# 31813C.net
KiCad netlist of a schematic drawn in EAGLE
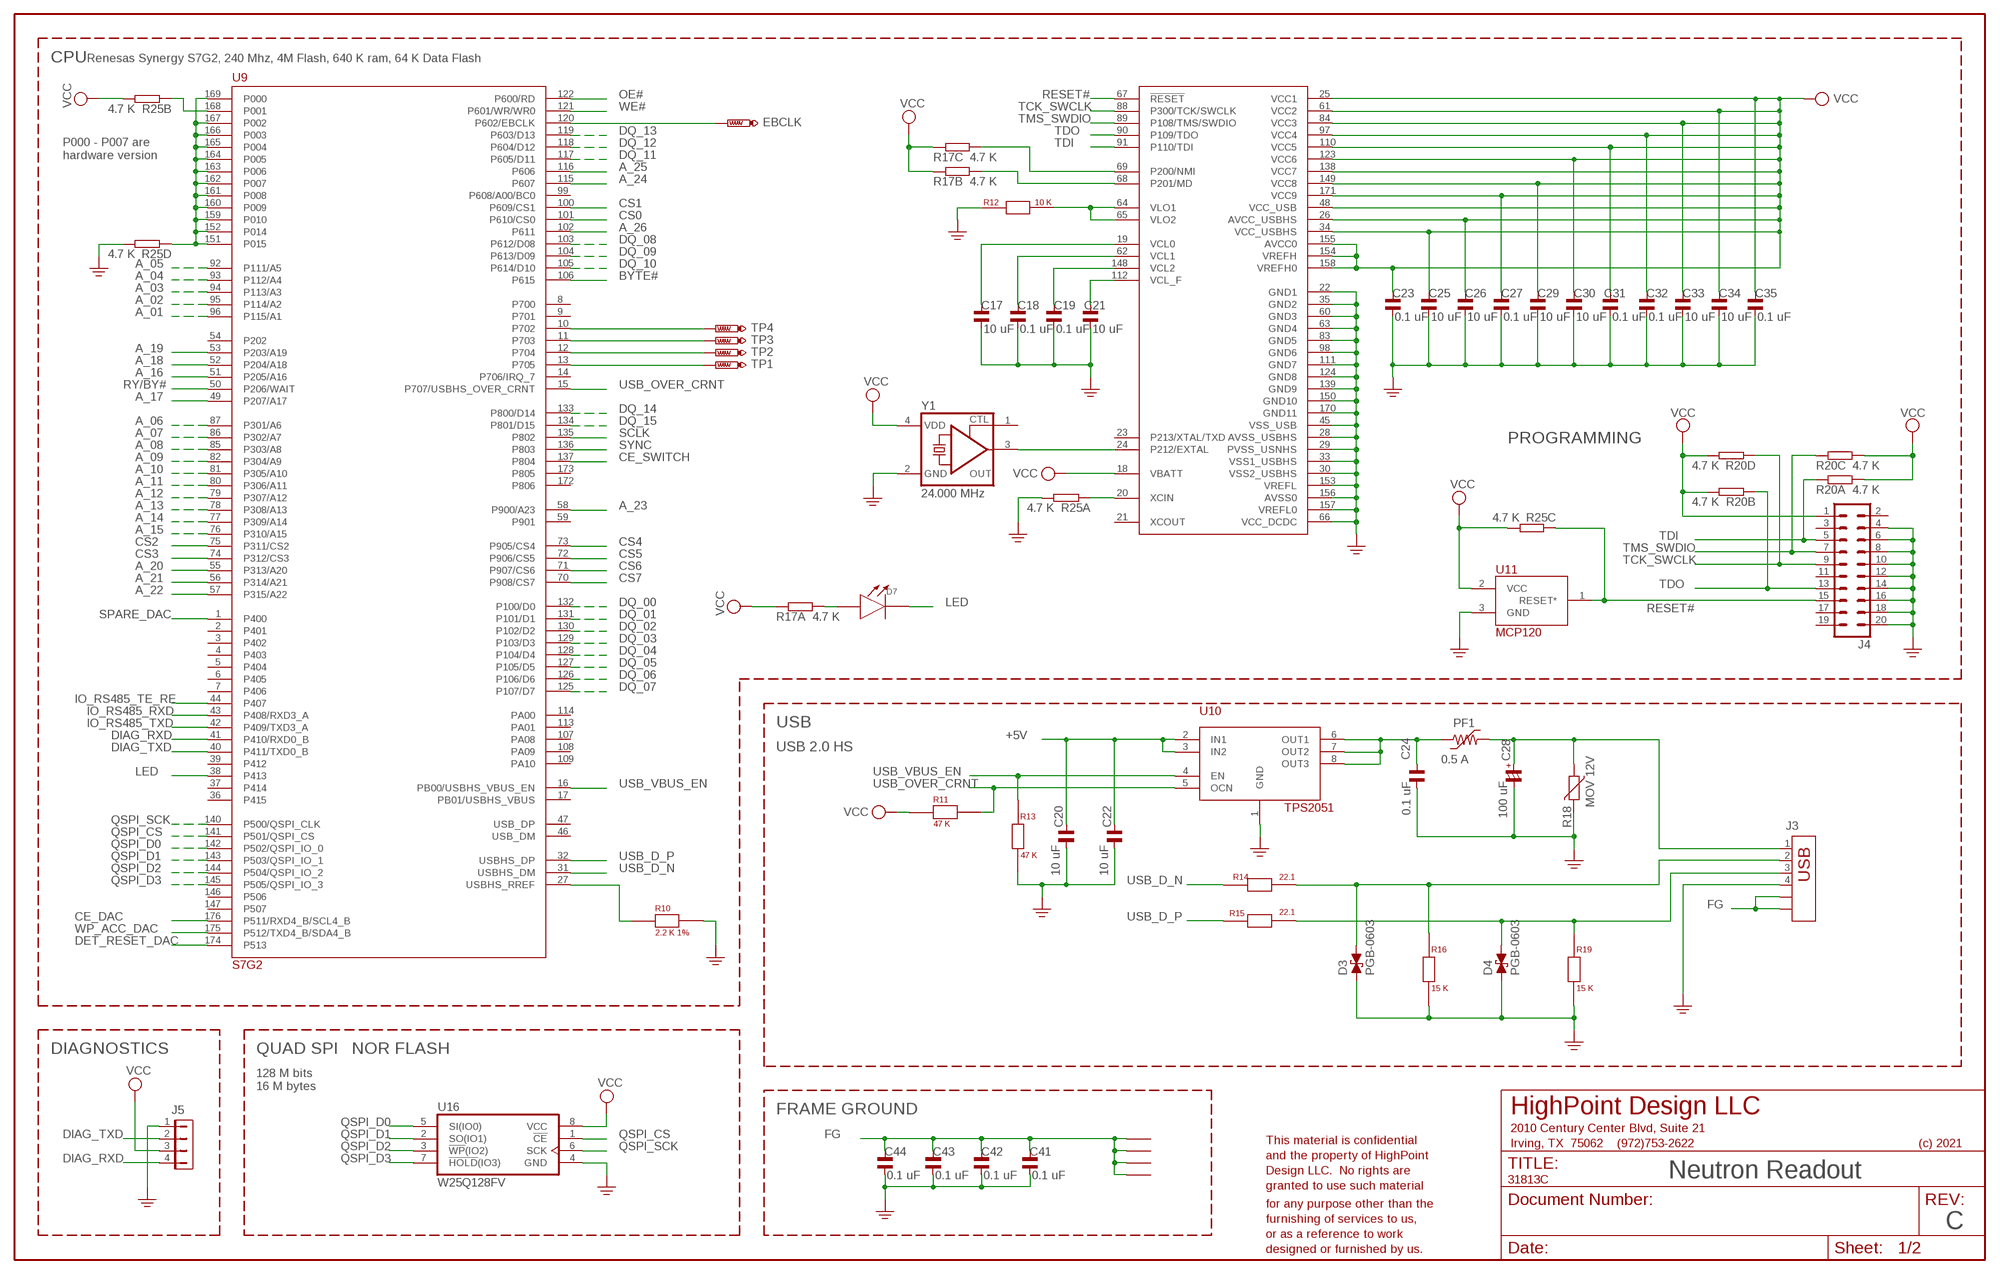
[diagram p0: schematic, sheet 1]
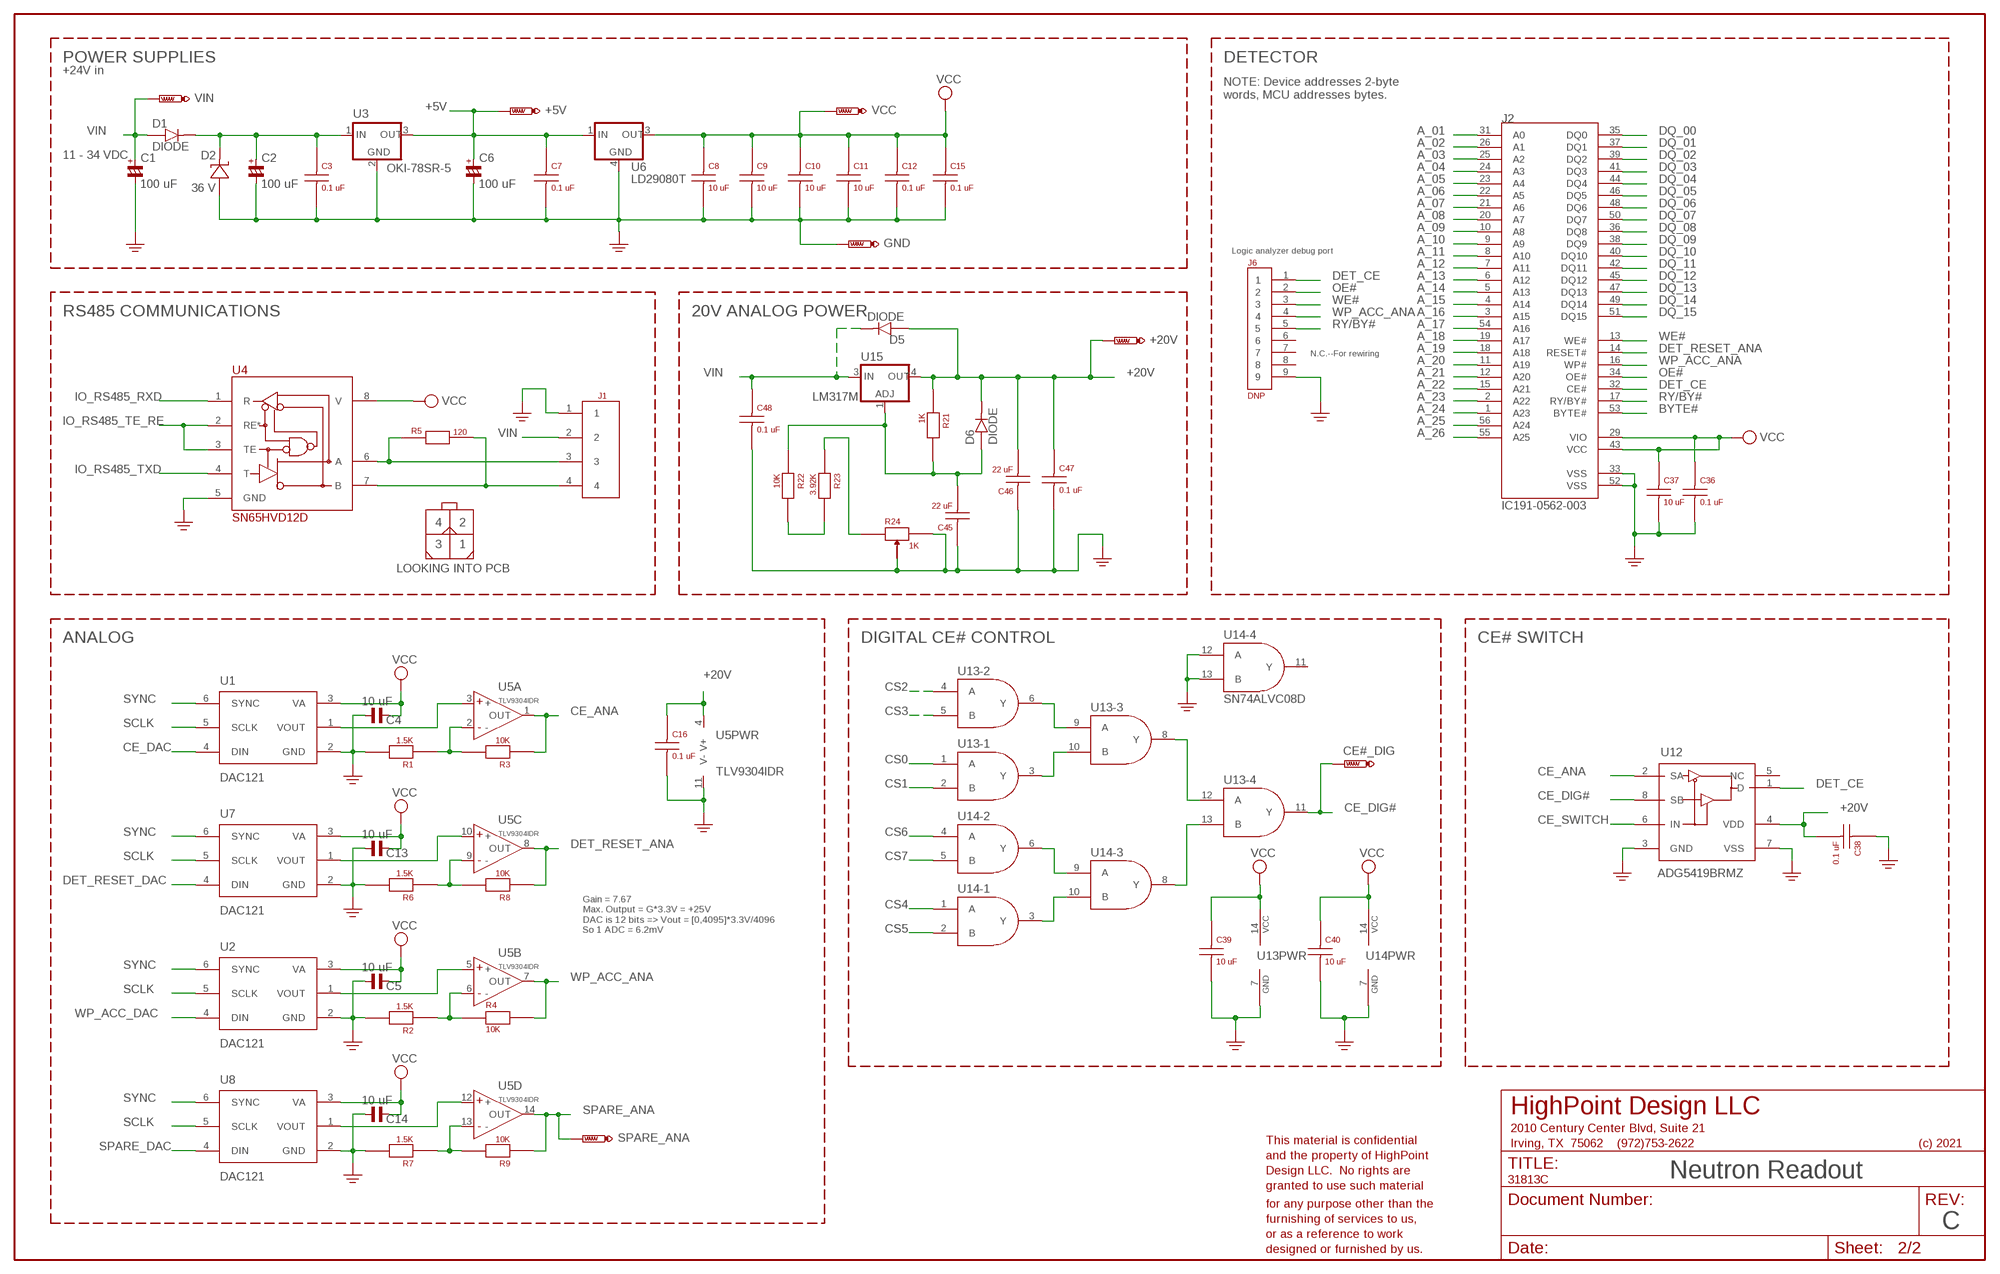
[diagram p1: schematic, sheet 2]

(export (version "E")
  (design (tool "Eeschema 10.0.6"))
  (components
    (comp (ref "+5V")
      (value "TP")
      (footprint "eagle-import:TP8040")
      (libsource (lib "eagle-import") (part "TP"))
    )
    (comp (ref "+20V")
      (value "TP")
      (footprint "eagle-import:TP8040")
      (libsource (lib "eagle-import") (part "TP"))
    )
    (comp (ref "C1")
      (value "100 uF")
      (footprint "eagle-import:CSV-E_F")
      (libsource (lib "eagle-import") (part "CAP_POL-E"))
    )
    (comp (ref "C2")
      (value "100 uF")
      (footprint "eagle-import:CSV-E_F")
      (libsource (lib "eagle-import") (part "CAP_POL-E"))
    )
    (comp (ref "C3")
      (value "0.1 uF")
      (footprint "eagle-import:0603")
      (libsource (lib "eagle-import") (part "CAP-0603"))
    )
    (comp (ref "C4")
      (value "10 uF")
      (footprint "eagle-import:0603")
      (libsource (lib "eagle-import") (part "CAP_SMD-0603"))
    )
    (comp (ref "C5")
      (value "10 uF")
      (footprint "eagle-import:0603")
      (libsource (lib "eagle-import") (part "CAP_SMD-0603"))
    )
    (comp (ref "C6")
      (value "100 uF")
      (footprint "eagle-import:CSV-E_F")
      (libsource (lib "eagle-import") (part "CAP_POL-E"))
    )
    (comp (ref "C7")
      (value "0.1 uF")
      (footprint "eagle-import:0603")
      (libsource (lib "eagle-import") (part "CAP-0603"))
    )
    (comp (ref "C8")
      (value "10 uF")
      (footprint "eagle-import:0603")
      (libsource (lib "eagle-import") (part "CAP-0603"))
    )
    (comp (ref "C9")
      (value "10 uF")
      (footprint "eagle-import:0603")
      (libsource (lib "eagle-import") (part "CAP-0603"))
    )
    (comp (ref "C10")
      (value "10 uF")
      (footprint "eagle-import:0603")
      (libsource (lib "eagle-import") (part "CAP-0603"))
    )
    (comp (ref "C11")
      (value "10 uF")
      (footprint "eagle-import:0603")
      (libsource (lib "eagle-import") (part "CAP-0603"))
    )
    (comp (ref "C12")
      (value "0.1 uF")
      (footprint "eagle-import:0603")
      (libsource (lib "eagle-import") (part "CAP-0603"))
    )
    (comp (ref "C13")
      (value "10 uF")
      (footprint "eagle-import:0603")
      (libsource (lib "eagle-import") (part "CAP_SMD-0603"))
    )
    (comp (ref "C14")
      (value "10 uF")
      (footprint "eagle-import:0603")
      (libsource (lib "eagle-import") (part "CAP_SMD-0603"))
    )
    (comp (ref "C15")
      (value "0.1 uF")
      (footprint "eagle-import:0603")
      (libsource (lib "eagle-import") (part "CAP-0603"))
    )
    (comp (ref "C16")
      (value "0.1 uF")
      (footprint "eagle-import:0603")
      (libsource (lib "eagle-import") (part "CAP-0603"))
    )
    (comp (ref "C36")
      (value "0.1 uF")
      (footprint "eagle-import:0603")
      (libsource (lib "eagle-import") (part "CAP-0603"))
    )
    (comp (ref "C37")
      (value "10 uF")
      (footprint "eagle-import:0603")
      (libsource (lib "eagle-import") (part "CAP-0603"))
    )
    (comp (ref "C38")
      (value "0.1 uF")
      (footprint "eagle-import:0603")
      (libsource (lib "eagle-import") (part "CAP-0603"))
    )
    (comp (ref "C39")
      (value "10 uF")
      (footprint "eagle-import:0603")
      (libsource (lib "eagle-import") (part "CAP-0603"))
    )
    (comp (ref "C40")
      (value "10 uF")
      (footprint "eagle-import:0603")
      (libsource (lib "eagle-import") (part "CAP-0603"))
    )
    (comp (ref "C45")
      (value "22 uF")
      (footprint "eagle-import:C1206")
      (libsource (lib "eagle-import") (part "CAP-1206"))
    )
    (comp (ref "C46")
      (value "22 uF")
      (footprint "eagle-import:C1206")
      (libsource (lib "eagle-import") (part "CAP-1206"))
    )
    (comp (ref "C47")
      (value "0.1 uF")
      (footprint "eagle-import:0603")
      (libsource (lib "eagle-import") (part "CAP-0603"))
    )
    (comp (ref "C48")
      (value "0.1 uF")
      (footprint "eagle-import:0603")
      (libsource (lib "eagle-import") (part "CAP-0603"))
    )
    (comp (ref "CE#_DIG")
      (value "TP")
      (footprint "eagle-import:TP8040")
      (libsource (lib "eagle-import") (part "TP"))
    )
    (comp (ref "D1")
      (value "DIODE")
      (footprint "eagle-import:SOD-123_MINI-SMA")
      (libsource (lib "eagle-import") (part "DIODE"))
    )
    (comp (ref "D2")
      (value "36 V")
      (footprint "eagle-import:SMB")
      (libsource (lib "eagle-import") (part "TRANSORB"))
    )
    (comp (ref "D5")
      (value "DIODE")
      (footprint "eagle-import:SOD-123_MINI-SMA")
      (libsource (lib "eagle-import") (part "DIODE"))
    )
    (comp (ref "D6")
      (value "DIODE")
      (footprint "eagle-import:SOD-123_MINI-SMA")
      (libsource (lib "eagle-import") (part "DIODE"))
    )
    (comp (ref "GND")
      (value "TP")
      (footprint "eagle-import:TP8040")
      (libsource (lib "eagle-import") (part "TP"))
    )
    (comp (ref "J1")
      (value "MICRO-FIT-4POS")
      (footprint "eagle-import:43045-0412")
      (libsource (lib "eagle-import") (part "MICRO-FIT-4POS"))
    )
    (comp (ref "J2")
      (value "IC191-0562-003")
      (footprint "eagle-import:IC1910562003")
      (fields (field (name "MOUSER_PART_NUMBER") "945-IC191-0562-003"))
      (libsource (lib "eagle-import") (part "IC191-0562-003"))
    )
    (comp (ref "J6")
      (value "DNP")
      (footprint "eagle-import:9P-100")
      (libsource (lib "eagle-import") (part "CON-9P-100"))
    )
    (comp (ref "R1")
      (value "1.5K")
      (footprint "eagle-import:0603")
      (libsource (lib "eagle-import") (part "RES-0603-H"))
    )
    (comp (ref "R2")
      (value "1.5K")
      (footprint "eagle-import:0603")
      (libsource (lib "eagle-import") (part "RES-0603-H"))
    )
    (comp (ref "R3")
      (value "10K")
      (footprint "eagle-import:0603")
      (libsource (lib "eagle-import") (part "RES-0603-H"))
    )
    (comp (ref "R4")
      (value "10K")
      (footprint "eagle-import:0603")
      (libsource (lib "eagle-import") (part "RES-0603-H"))
    )
    (comp (ref "R5")
      (value "120")
      (footprint "eagle-import:0603")
      (libsource (lib "eagle-import") (part "RES-0603-H"))
    )
    (comp (ref "R6")
      (value "1.5K")
      (footprint "eagle-import:0603")
      (libsource (lib "eagle-import") (part "RES-0603-H"))
    )
    (comp (ref "R7")
      (value "1.5K")
      (footprint "eagle-import:0603")
      (libsource (lib "eagle-import") (part "RES-0603-H"))
    )
    (comp (ref "R8")
      (value "10K")
      (footprint "eagle-import:0603")
      (libsource (lib "eagle-import") (part "RES-0603-H"))
    )
    (comp (ref "R9")
      (value "10K")
      (footprint "eagle-import:0603")
      (libsource (lib "eagle-import") (part "RES-0603-H"))
    )
    (comp (ref "R21")
      (value "1K")
      (footprint "eagle-import:0603")
      (libsource (lib "eagle-import") (part "RES-0603-H"))
    )
    (comp (ref "R22")
      (value "10K")
      (footprint "eagle-import:0603")
      (libsource (lib "eagle-import") (part "RES-0603-H"))
    )
    (comp (ref "R23")
      (value "3.92K")
      (footprint "eagle-import:0603")
      (libsource (lib "eagle-import") (part "RES-0603-H"))
    )
    (comp (ref "R24")
      (value "1K")
      (footprint "eagle-import:POT-V10")
      (libsource (lib "eagle-import") (part "PT10XV10"))
    )
    (comp (ref "SPARE_ANA")
      (value "TP")
      (footprint "eagle-import:TP8040")
      (libsource (lib "eagle-import") (part "TP"))
    )
    (comp (ref "U1")
      (value "DAC121")
      (footprint "eagle-import:SOT23-6")
      (libsource (lib "eagle-import") (part "DAC121"))
    )
    (comp (ref "U2")
      (value "DAC121")
      (footprint "eagle-import:SOT23-6")
      (libsource (lib "eagle-import") (part "DAC121"))
    )
    (comp (ref "U3")
      (value "OKI-78SR-5")
      (footprint "eagle-import:PS-OKI-78SR")
      (libsource (lib "eagle-import") (part "PS-OKI-78SR"))
    )
    (comp (ref "U4")
      (value "SN65HVD12D")
      (footprint "eagle-import:SOIC-08-150")
      (libsource (lib "eagle-import") (part "SN65HVD12D"))
    )
    (comp (ref "U5")
      (value "TLV9304IDR")
      (footprint "eagle-import:SO14")
      (libsource (lib "eagle-import") (part "TLV9304IDR"))
    )
    (comp (ref "U6")
      (value "LD29080T")
      (footprint "eagle-import:DPAK")
      (libsource (lib "eagle-import") (part "LD29080T"))
    )
    (comp (ref "U7")
      (value "DAC121")
      (footprint "eagle-import:SOT23-6")
      (libsource (lib "eagle-import") (part "DAC121"))
    )
    (comp (ref "U8")
      (value "DAC121")
      (footprint "eagle-import:SOT23-6")
      (libsource (lib "eagle-import") (part "DAC121"))
    )
    (comp (ref "U12")
      (value "ADG5419BRMZ")
      (footprint "eagle-import:RM_8_ADI")
      (libsource (lib "eagle-import") (part "ADG5419BRMZ"))
    )
    (comp (ref "U13")
      (value "SN74ALVC08D")
      (footprint "eagle-import:D14")
      (fields
        (field (name "GENERIC_PART_NUMBER") "SN74ALVC08")
        (field (name "MANUFACTURER") "Texas Instruments")
      )
      (libsource (lib "eagle-import") (part "SN74ALVC08D"))
    )
    (comp (ref "U14")
      (value "SN74ALVC08D")
      (footprint "eagle-import:D14")
      (fields
        (field (name "GENERIC_PART_NUMBER") "SN74ALVC08")
        (field (name "MANUFACTURER") "Texas Instruments")
      )
      (libsource (lib "eagle-import") (part "SN74ALVC08D"))
    )
    (comp (ref "U15")
      (value "LM317M")
      (footprint "eagle-import:DPAK")
      (libsource (lib "eagle-import") (part "LM317M"))
    )
    (comp (ref "VCC")
      (value "TP")
      (footprint "eagle-import:TP8040")
      (libsource (lib "eagle-import") (part "TP"))
    )
    (comp (ref "VIN")
      (value "TP")
      (footprint "eagle-import:TP8040")
      (libsource (lib "eagle-import") (part "TP"))
    )
    (comp (ref "C17")
      (value "10 uF")
      (footprint "eagle-import:0603")
      (libsource (lib "eagle-import") (part "CAP_SMD-0603"))
    )
    (comp (ref "C18")
      (value "0.1 uF")
      (footprint "eagle-import:0603")
      (libsource (lib "eagle-import") (part "CAP_SMD-0603"))
    )
    (comp (ref "C19")
      (value "0.1 uF")
      (footprint "eagle-import:0603")
      (libsource (lib "eagle-import") (part "CAP_SMD-0603"))
    )
    (comp (ref "C20")
      (value "10 uF")
      (footprint "eagle-import:0603")
      (libsource (lib "eagle-import") (part "CAP_SMD-0603"))
    )
    (comp (ref "C21")
      (value "10 uF")
      (footprint "eagle-import:0603")
      (libsource (lib "eagle-import") (part "CAP_SMD-0603"))
    )
    (comp (ref "C22")
      (value "10 uF")
      (footprint "eagle-import:0603")
      (libsource (lib "eagle-import") (part "CAP_SMD-0603"))
    )
    (comp (ref "C23")
      (value "0.1 uF")
      (footprint "eagle-import:0603")
      (libsource (lib "eagle-import") (part "CAP_SMD-0603"))
    )
    (comp (ref "C24")
      (value "0.1 uF")
      (footprint "eagle-import:0603")
      (libsource (lib "eagle-import") (part "CAP_SMD-0603"))
    )
    (comp (ref "C25")
      (value "10 uF")
      (footprint "eagle-import:0603")
      (libsource (lib "eagle-import") (part "CAP_SMD-0603"))
    )
    (comp (ref "C26")
      (value "10 uF")
      (footprint "eagle-import:0603")
      (libsource (lib "eagle-import") (part "CAP_SMD-0603"))
    )
    (comp (ref "C27")
      (value "0.1 uF")
      (footprint "eagle-import:0603")
      (libsource (lib "eagle-import") (part "CAP_SMD-0603"))
    )
    (comp (ref "C28")
      (value "100 uF")
      (footprint "eagle-import:CSV-E_F")
      (libsource (lib "eagle-import") (part "CAP_POL-E"))
    )
    (comp (ref "C29")
      (value "10 uF")
      (footprint "eagle-import:0603")
      (libsource (lib "eagle-import") (part "CAP_SMD-0603"))
    )
    (comp (ref "C30")
      (value "10 uF")
      (footprint "eagle-import:0603")
      (libsource (lib "eagle-import") (part "CAP_SMD-0603"))
    )
    (comp (ref "C31")
      (value "0.1 uF")
      (footprint "eagle-import:0603")
      (libsource (lib "eagle-import") (part "CAP_SMD-0603"))
    )
    (comp (ref "C32")
      (value "0.1 uF")
      (footprint "eagle-import:0603")
      (libsource (lib "eagle-import") (part "CAP_SMD-0603"))
    )
    (comp (ref "C33")
      (value "10 uF")
      (footprint "eagle-import:0603")
      (libsource (lib "eagle-import") (part "CAP_SMD-0603"))
    )
    (comp (ref "C34")
      (value "10 uF")
      (footprint "eagle-import:0603")
      (libsource (lib "eagle-import") (part "CAP_SMD-0603"))
    )
    (comp (ref "C35")
      (value "0.1 uF")
      (footprint "eagle-import:0603")
      (libsource (lib "eagle-import") (part "CAP_SMD-0603"))
    )
    (comp (ref "C41")
      (value "0.1 uF")
      (footprint "eagle-import:0603")
      (libsource (lib "eagle-import") (part "CAP_SMD-0603"))
    )
    (comp (ref "C42")
      (value "0.1 uF")
      (footprint "eagle-import:0603")
      (libsource (lib "eagle-import") (part "CAP_SMD-0603"))
    )
    (comp (ref "C43")
      (value "0.1 uF")
      (footprint "eagle-import:0603")
      (libsource (lib "eagle-import") (part "CAP_SMD-0603"))
    )
    (comp (ref "C44")
      (value "0.1 uF")
      (footprint "eagle-import:0603")
      (libsource (lib "eagle-import") (part "CAP_SMD-0603"))
    )
    (comp (ref "D3")
      (value "PGB-0603")
      (footprint "eagle-import:PGB-0603")
      (libsource (lib "eagle-import") (part "PGB-0603"))
    )
    (comp (ref "D4")
      (value "PGB-0603")
      (footprint "eagle-import:PGB-0603")
      (libsource (lib "eagle-import") (part "PGB-0603"))
    )
    (comp (ref "D7")
      (value "LED0805")
      (footprint "eagle-import:D0805")
      (libsource (lib "eagle-import") (part "LED0805"))
    )
    (comp (ref "EBCLK")
      (value "TP")
      (footprint "eagle-import:TP8040")
      (libsource (lib "eagle-import") (part "TP"))
    )
    (comp (ref "J3")
      (value "CON-USB-292303-1")
      (footprint "eagle-import:USB")
      (libsource (lib "eagle-import") (part "CON-USB-292303-1"))
    )
    (comp (ref "J4")
      (value "ML20")
      (footprint "eagle-import:ML20")
      (libsource (lib "eagle-import") (part "ML20"))
    )
    (comp (ref "J5")
      (value "MTA04")
      (footprint "eagle-import:MTA04-100")
      (libsource (lib "eagle-import") (part "MTA04"))
    )
    (comp (ref "M1")
      (value "MNT-125")
      (footprint "eagle-import:MNT-125")
      (libsource (lib "eagle-import") (part "MNT-125"))
    )
    (comp (ref "M2")
      (value "MNT-125")
      (footprint "eagle-import:MNT-125")
      (libsource (lib "eagle-import") (part "MNT-125"))
    )
    (comp (ref "M3")
      (value "MNT-125")
      (footprint "eagle-import:MNT-125")
      (libsource (lib "eagle-import") (part "MNT-125"))
    )
    (comp (ref "M4")
      (value "MNT-125")
      (footprint "eagle-import:MNT-125")
      (libsource (lib "eagle-import") (part "MNT-125"))
    )
    (comp (ref "PF1")
      (value "0.5 A")
      (footprint "eagle-import:F1206")
      (libsource (lib "eagle-import") (part "PTC-F1206"))
    )
    (comp (ref "R10")
      (value "2.2 K 1%")
      (footprint "eagle-import:0603")
      (libsource (lib "eagle-import") (part "RES-0603-H"))
    )
    (comp (ref "R11")
      (value "47 K")
      (footprint "eagle-import:0603")
      (libsource (lib "eagle-import") (part "RES-0603-H"))
    )
    (comp (ref "R12")
      (value "10 K")
      (footprint "eagle-import:0603")
      (libsource (lib "eagle-import") (part "RES-0603-H"))
    )
    (comp (ref "R13")
      (value "47 K")
      (footprint "eagle-import:0603")
      (libsource (lib "eagle-import") (part "RES-0603-V"))
    )
    (comp (ref "R14")
      (value "22.1")
      (footprint "eagle-import:0603")
      (libsource (lib "eagle-import") (part "RES-0603-H"))
    )
    (comp (ref "R15")
      (value "22.1")
      (footprint "eagle-import:0603")
      (libsource (lib "eagle-import") (part "RES-0603-H"))
    )
    (comp (ref "R16")
      (value "15 K")
      (footprint "eagle-import:0603")
      (libsource (lib "eagle-import") (part "RES-0603-V"))
    )
    (comp (ref "R17")
      (value "4.7 K")
      (footprint "eagle-import:RNET-4R-38V")
      (libsource (lib "eagle-import") (part "R_38V"))
    )
    (comp (ref "R18")
      (value "MOV 12V")
      (footprint "eagle-import:R0603")
      (libsource (lib "eagle-import") (part "VARISTOR-0603"))
    )
    (comp (ref "R19")
      (value "15 K")
      (footprint "eagle-import:0603")
      (libsource (lib "eagle-import") (part "RES-0603-V"))
    )
    (comp (ref "R20")
      (value "4.7 K")
      (footprint "eagle-import:RNET-4R-38V")
      (libsource (lib "eagle-import") (part "R_38V"))
    )
    (comp (ref "R25")
      (value "4.7 K")
      (footprint "eagle-import:RNET-4R-38V")
      (libsource (lib "eagle-import") (part "R_38V"))
    )
    (comp (ref "TP1")
      (value "TP")
      (footprint "eagle-import:TP8040")
      (libsource (lib "eagle-import") (part "TP"))
    )
    (comp (ref "TP2")
      (value "TP")
      (footprint "eagle-import:TP8040")
      (libsource (lib "eagle-import") (part "TP"))
    )
    (comp (ref "TP3")
      (value "TP")
      (footprint "eagle-import:TP8040")
      (libsource (lib "eagle-import") (part "TP"))
    )
    (comp (ref "TP4")
      (value "TP")
      (footprint "eagle-import:TP8040")
      (libsource (lib "eagle-import") (part "TP"))
    )
    (comp (ref "U9")
      (value "S7G2")
      (footprint "eagle-import:LQFP176")
      (libsource (lib "eagle-import") (part "S7G2-176"))
    )
    (comp (ref "U10")
      (value "TPS2051")
      (footprint "eagle-import:SOIC-8-SPECIAL")
      (libsource (lib "eagle-import") (part "TPS2051"))
    )
    (comp (ref "U11")
      (value "MCP120")
      (footprint "eagle-import:SOT23")
      (libsource (lib "eagle-import") (part "MCP120"))
    )
    (comp (ref "U16")
      (value "W25Q128FV")
      (footprint "eagle-import:SO08-JB")
      (libsource (lib "eagle-import") (part "IS25LQ080B-JB"))
    )
    (comp (ref "Y1")
      (value "24.000 MHz")
      (footprint "eagle-import:ASFL1")
      (libsource (lib "eagle-import") (part "ASFL1"))
    )
  )
  (nets
    (net (code "1") (name "+5V") (class "Default")
      (node (ref "+5V") (pin "1") (pinfunction "TP_1") (pintype "input"))
      (node (ref "C20") (pin "2") (pinfunction "2_2") (pintype "passive"))
      (node (ref "C22") (pin "2") (pinfunction "2_2") (pintype "passive"))
      (node (ref "C6") (pin "+") (pinfunction "+_+") (pintype "passive"))
      (node (ref "C7") (pin "1") (pinfunction "P$1_1") (pintype "bidirectional"))
      (node (ref "U10") (pin "2") (pinfunction "IN1_2") (pintype "bidirectional"))
      (node (ref "U10") (pin "3") (pinfunction "IN2_3") (pintype "bidirectional"))
      (node (ref "U3") (pin "3") (pinfunction "OUT_3") (pintype "passive"))
      (node (ref "U6") (pin "1") (pinfunction "IN_1") (pintype "input"))
    )
    (net (code "2") (name "+20V") (class "Default")
      (node (ref "+20V") (pin "1") (pinfunction "TP_1") (pintype "input"))
      (node (ref "C16") (pin "1") (pinfunction "P$1_1") (pintype "bidirectional"))
      (node (ref "C38") (pin "2") (pinfunction "P$2_2") (pintype "bidirectional"))
      (node (ref "C46") (pin "2") (pinfunction "P$2_2") (pintype "bidirectional"))
      (node (ref "C47") (pin "1") (pinfunction "P$1_1") (pintype "bidirectional"))
      (node (ref "D5") (pin "A") (pinfunction "A_A") (pintype "passive"))
      (node (ref "D6") (pin "C") (pinfunction "C_C") (pintype "passive"))
      (node (ref "R21") (pin "1") (pinfunction "P$1_1") (pintype "bidirectional"))
      (node (ref "U12") (pin "4") (pinfunction "VDD_4") (pintype "passive"))
      (node (ref "U15") (pin "4") (pinfunction "OUT_4") (pintype "passive"))
      (node (ref "U5") (pin "4") (pinfunction "V+_4") (pintype "power_in"))
    )
    (net (code "3") (name "A_01") (class "Default")
      (node (ref "J2") (pin "31") (pinfunction "A0_31") (pintype "input"))
      (node (ref "U9") (pin "96") (pinfunction "P115/A1_96") (pintype "bidirectional"))
    )
    (net (code "4") (name "A_02") (class "Default")
      (node (ref "J2") (pin "26") (pinfunction "A1_26") (pintype "input"))
      (node (ref "U9") (pin "95") (pinfunction "P114/A2_95") (pintype "bidirectional"))
    )
    (net (code "5") (name "A_03") (class "Default")
      (node (ref "J2") (pin "25") (pinfunction "A2_25") (pintype "input"))
      (node (ref "U9") (pin "94") (pinfunction "P113/A3_94") (pintype "bidirectional"))
    )
    (net (code "6") (name "A_04") (class "Default")
      (node (ref "J2") (pin "24") (pinfunction "A3_24") (pintype "input"))
      (node (ref "U9") (pin "93") (pinfunction "P112/A4_93") (pintype "bidirectional"))
    )
    (net (code "7") (name "A_05") (class "Default")
      (node (ref "J2") (pin "23") (pinfunction "A4_23") (pintype "input"))
      (node (ref "U9") (pin "92") (pinfunction "P111/A5_92") (pintype "bidirectional"))
    )
    (net (code "8") (name "A_06") (class "Default")
      (node (ref "J2") (pin "22") (pinfunction "A5_22") (pintype "input"))
      (node (ref "U9") (pin "87") (pinfunction "P301/A6_87") (pintype "bidirectional"))
    )
    (net (code "9") (name "A_07") (class "Default")
      (node (ref "J2") (pin "21") (pinfunction "A6_21") (pintype "input"))
      (node (ref "U9") (pin "86") (pinfunction "P302/A7_86") (pintype "bidirectional"))
    )
    (net (code "10") (name "A_08") (class "Default")
      (node (ref "J2") (pin "20") (pinfunction "A7_20") (pintype "input"))
      (node (ref "U9") (pin "85") (pinfunction "P303/A8_85") (pintype "bidirectional"))
    )
    (net (code "11") (name "A_09") (class "Default")
      (node (ref "J2") (pin "10") (pinfunction "A8_10") (pintype "input"))
      (node (ref "U9") (pin "82") (pinfunction "P304/A9_82") (pintype "bidirectional"))
    )
    (net (code "12") (name "A_10") (class "Default")
      (node (ref "J2") (pin "9") (pinfunction "A9_9") (pintype "input"))
      (node (ref "U9") (pin "81") (pinfunction "P305/A10_81") (pintype "bidirectional"))
    )
    (net (code "13") (name "A_11") (class "Default")
      (node (ref "J2") (pin "8") (pinfunction "A10_8") (pintype "input"))
      (node (ref "U9") (pin "80") (pinfunction "P306/A11_80") (pintype "bidirectional"))
    )
    (net (code "14") (name "A_12") (class "Default")
      (node (ref "J2") (pin "7") (pinfunction "A11_7") (pintype "input"))
      (node (ref "U9") (pin "79") (pinfunction "P307/A12_79") (pintype "bidirectional"))
    )
    (net (code "15") (name "A_13") (class "Default")
      (node (ref "J2") (pin "6") (pinfunction "A12_6") (pintype "input"))
      (node (ref "U9") (pin "78") (pinfunction "P308/A13_78") (pintype "bidirectional"))
    )
    (net (code "16") (name "A_14") (class "Default")
      (node (ref "J2") (pin "5") (pinfunction "A13_5") (pintype "input"))
      (node (ref "U9") (pin "77") (pinfunction "P309/A14_77") (pintype "bidirectional"))
    )
    (net (code "17") (name "A_15") (class "Default")
      (node (ref "J2") (pin "4") (pinfunction "A14_4") (pintype "input"))
      (node (ref "U9") (pin "76") (pinfunction "P310/A15_76") (pintype "bidirectional"))
    )
    (net (code "18") (name "A_16") (class "Default")
      (node (ref "J2") (pin "3") (pinfunction "A15_3") (pintype "input"))
      (node (ref "U9") (pin "51") (pinfunction "P205/A16_51") (pintype "bidirectional"))
    )
    (net (code "19") (name "A_17") (class "Default")
      (node (ref "J2") (pin "54") (pinfunction "A16_54") (pintype "input"))
      (node (ref "U9") (pin "49") (pinfunction "P207/A17_49") (pintype "bidirectional"))
    )
    (net (code "20") (name "A_18") (class "Default")
      (node (ref "J2") (pin "19") (pinfunction "A17_19") (pintype "input"))
      (node (ref "U9") (pin "52") (pinfunction "P204/A18_52") (pintype "bidirectional"))
    )
    (net (code "21") (name "A_19") (class "Default")
      (node (ref "J2") (pin "18") (pinfunction "A18_18") (pintype "input"))
      (node (ref "U9") (pin "53") (pinfunction "P203/A19_53") (pintype "bidirectional"))
    )
    (net (code "22") (name "A_20") (class "Default")
      (node (ref "J2") (pin "11") (pinfunction "A19_11") (pintype "input"))
      (node (ref "U9") (pin "55") (pinfunction "P313/A20_55") (pintype "bidirectional"))
    )
    (net (code "23") (name "A_21") (class "Default")
      (node (ref "J2") (pin "12") (pinfunction "A20_12") (pintype "input"))
      (node (ref "U9") (pin "56") (pinfunction "P314/A21_56") (pintype "bidirectional"))
    )
    (net (code "24") (name "A_22") (class "Default")
      (node (ref "J2") (pin "15") (pinfunction "A21_15") (pintype "input"))
      (node (ref "U9") (pin "57") (pinfunction "P315/A22_57") (pintype "bidirectional"))
    )
    (net (code "25") (name "A_23") (class "Default")
      (node (ref "J2") (pin "2") (pinfunction "A22_2") (pintype "input"))
      (node (ref "U9") (pin "58") (pinfunction "P900/A23_58") (pintype "bidirectional"))
    )
    (net (code "26") (name "A_24") (class "Default")
      (node (ref "J2") (pin "1") (pinfunction "A23_1") (pintype "input"))
      (node (ref "U9") (pin "115") (pinfunction "P607_115") (pintype "bidirectional"))
    )
    (net (code "27") (name "A_25") (class "Default")
      (node (ref "J2") (pin "56") (pinfunction "A24_56") (pintype "input"))
      (node (ref "U9") (pin "116") (pinfunction "P606_116") (pintype "bidirectional"))
    )
    (net (code "28") (name "A_26") (class "Default")
      (node (ref "J2") (pin "55") (pinfunction "A25_55") (pintype "input"))
      (node (ref "U9") (pin "102") (pinfunction "P611_102") (pintype "bidirectional"))
    )
    (net (code "29") (name "BYTE#") (class "Default")
      (node (ref "J2") (pin "53") (pinfunction "BYTE#_53") (pintype "input"))
      (node (ref "U9") (pin "106") (pinfunction "P615_106") (pintype "bidirectional"))
    )
    (net (code "30") (name "CE_ANA") (class "Default")
      (node (ref "R3") (pin "1") (pinfunction "P$1_1") (pintype "bidirectional"))
      (node (ref "U12") (pin "2") (pinfunction "SA_2") (pintype "passive"))
      (node (ref "U5") (pin "1") (pinfunction "OUT_1") (pintype "output"))
    )
    (net (code "31") (name "CE_DAC") (class "Default")
      (node (ref "U1") (pin "4") (pinfunction "DIN_4") (pintype "input"))
      (node (ref "U9") (pin "176") (pinfunction "P511/RXD4_B/SCL4_B_176") (pintype "bidirectional"))
    )
    (net (code "32") (name "CE_DIG#") (class "Default")
      (node (ref "CE#_DIG") (pin "1") (pinfunction "TP_1") (pintype "input"))
      (node (ref "U12") (pin "8") (pinfunction "SB_8") (pintype "passive"))
      (node (ref "U13") (pin "11") (pinfunction "Y_11") (pintype "output"))
    )
    (net (code "33") (name "CE_SWITCH") (class "Default")
      (node (ref "U12") (pin "6") (pinfunction "IN_6") (pintype "passive"))
      (node (ref "U9") (pin "137") (pinfunction "P804_137") (pintype "bidirectional"))
    )
    (net (code "34") (name "CS0") (class "Default")
      (node (ref "U13") (pin "1") (pinfunction "A_1") (pintype "input"))
      (node (ref "U9") (pin "101") (pinfunction "P610/CS0_101") (pintype "bidirectional"))
    )
    (net (code "35") (name "CS1") (class "Default")
      (node (ref "U13") (pin "2") (pinfunction "B_2") (pintype "input"))
      (node (ref "U9") (pin "100") (pinfunction "P609/CS1_100") (pintype "bidirectional"))
    )
    (net (code "36") (name "CS2") (class "Default")
      (node (ref "U13") (pin "4") (pinfunction "A_4") (pintype "input"))
      (node (ref "U9") (pin "75") (pinfunction "P311/CS2_75") (pintype "bidirectional"))
    )
    (net (code "37") (name "CS3") (class "Default")
      (node (ref "U13") (pin "5") (pinfunction "B_5") (pintype "input"))
      (node (ref "U9") (pin "74") (pinfunction "P312/CS3_74") (pintype "bidirectional"))
    )
    (net (code "38") (name "CS4") (class "Default")
      (node (ref "U14") (pin "1") (pinfunction "A_1") (pintype "input"))
      (node (ref "U9") (pin "73") (pinfunction "P905/CS4_73") (pintype "bidirectional"))
    )
    (net (code "39") (name "CS5") (class "Default")
      (node (ref "U14") (pin "2") (pinfunction "B_2") (pintype "input"))
      (node (ref "U9") (pin "72") (pinfunction "P906/CS5_72") (pintype "bidirectional"))
    )
    (net (code "40") (name "CS6") (class "Default")
      (node (ref "U14") (pin "4") (pinfunction "A_4") (pintype "input"))
      (node (ref "U9") (pin "71") (pinfunction "P907/CS6_71") (pintype "bidirectional"))
    )
    (net (code "41") (name "CS7") (class "Default")
      (node (ref "U14") (pin "5") (pinfunction "B_5") (pintype "input"))
      (node (ref "U9") (pin "70") (pinfunction "P908/CS7_70") (pintype "bidirectional"))
    )
    (net (code "42") (name "DET_CE") (class "Default")
      (node (ref "J2") (pin "32") (pinfunction "CE#_32") (pintype "input"))
      (node (ref "J6") (pin "1") (pinfunction "1_1") (pintype "passive"))
      (node (ref "U12") (pin "1") (pinfunction "D_1") (pintype "passive"))
    )
    (net (code "43") (name "DET_RESET_ANA") (class "Default")
      (node (ref "J2") (pin "14") (pinfunction "RESET#_14") (pintype "input"))
      (node (ref "R8") (pin "1") (pinfunction "P$1_1") (pintype "bidirectional"))
      (node (ref "U5") (pin "8") (pinfunction "OUT_8") (pintype "output"))
    )
    (net (code "44") (name "DET_RESET_DAC") (class "Default")
      (node (ref "U7") (pin "4") (pinfunction "DIN_4") (pintype "input"))
      (node (ref "U9") (pin "174") (pinfunction "P513_174") (pintype "bidirectional"))
    )
    (net (code "45") (name "DIAG_RXD") (class "Default")
      (node (ref "J5") (pin "4") (pinfunction "4_4") (pintype "passive"))
      (node (ref "U9") (pin "41") (pinfunction "P410/RXD0_B_41") (pintype "bidirectional"))
    )
    (net (code "46") (name "DIAG_TXD") (class "Default")
      (node (ref "J5") (pin "2") (pinfunction "2_2") (pintype "passive"))
      (node (ref "U9") (pin "40") (pinfunction "P411/TXD0_B_40") (pintype "bidirectional"))
    )
    (net (code "47") (name "DQ_00") (class "Default")
      (node (ref "J2") (pin "35") (pinfunction "DQ0_35") (pintype "bidirectional"))
      (node (ref "U9") (pin "132") (pinfunction "P100/D0_132") (pintype "bidirectional"))
    )
    (net (code "48") (name "DQ_01") (class "Default")
      (node (ref "J2") (pin "37") (pinfunction "DQ1_37") (pintype "bidirectional"))
      (node (ref "U9") (pin "131") (pinfunction "P101/D1_131") (pintype "bidirectional"))
    )
    (net (code "49") (name "DQ_02") (class "Default")
      (node (ref "J2") (pin "39") (pinfunction "DQ2_39") (pintype "bidirectional"))
      (node (ref "U9") (pin "130") (pinfunction "P102/D2_130") (pintype "bidirectional"))
    )
    (net (code "50") (name "DQ_03") (class "Default")
      (node (ref "J2") (pin "41") (pinfunction "DQ3_41") (pintype "bidirectional"))
      (node (ref "U9") (pin "129") (pinfunction "P103/D3_129") (pintype "bidirectional"))
    )
    (net (code "51") (name "DQ_04") (class "Default")
      (node (ref "J2") (pin "44") (pinfunction "DQ4_44") (pintype "bidirectional"))
      (node (ref "U9") (pin "128") (pinfunction "P104/D4_128") (pintype "bidirectional"))
    )
    (net (code "52") (name "DQ_05") (class "Default")
      (node (ref "J2") (pin "46") (pinfunction "DQ5_46") (pintype "bidirectional"))
      (node (ref "U9") (pin "127") (pinfunction "P105/D5_127") (pintype "bidirectional"))
    )
    (net (code "53") (name "DQ_06") (class "Default")
      (node (ref "J2") (pin "48") (pinfunction "DQ6_48") (pintype "bidirectional"))
      (node (ref "U9") (pin "126") (pinfunction "P106/D6_126") (pintype "bidirectional"))
    )
    (net (code "54") (name "DQ_07") (class "Default")
      (node (ref "J2") (pin "50") (pinfunction "DQ7_50") (pintype "bidirectional"))
      (node (ref "U9") (pin "125") (pinfunction "P107/D7_125") (pintype "bidirectional"))
    )
    (net (code "55") (name "DQ_08") (class "Default")
      (node (ref "J2") (pin "36") (pinfunction "DQ8_36") (pintype "bidirectional"))
      (node (ref "U9") (pin "103") (pinfunction "P612/D08_103") (pintype "bidirectional"))
    )
    (net (code "56") (name "DQ_09") (class "Default")
      (node (ref "J2") (pin "38") (pinfunction "DQ9_38") (pintype "bidirectional"))
      (node (ref "U9") (pin "104") (pinfunction "P613/D09_104") (pintype "bidirectional"))
    )
    (net (code "57") (name "DQ_10") (class "Default")
      (node (ref "J2") (pin "40") (pinfunction "DQ10_40") (pintype "bidirectional"))
      (node (ref "U9") (pin "105") (pinfunction "P614/D10_105") (pintype "bidirectional"))
    )
    (net (code "58") (name "DQ_11") (class "Default")
      (node (ref "J2") (pin "42") (pinfunction "DQ11_42") (pintype "bidirectional"))
      (node (ref "U9") (pin "117") (pinfunction "P605/D11_117") (pintype "bidirectional"))
    )
    (net (code "59") (name "DQ_12") (class "Default")
      (node (ref "J2") (pin "45") (pinfunction "DQ12_45") (pintype "bidirectional"))
      (node (ref "U9") (pin "118") (pinfunction "P604/D12_118") (pintype "bidirectional"))
    )
    (net (code "60") (name "DQ_13") (class "Default")
      (node (ref "J2") (pin "47") (pinfunction "DQ13_47") (pintype "bidirectional"))
      (node (ref "U9") (pin "119") (pinfunction "P603/D13_119") (pintype "bidirectional"))
    )
    (net (code "61") (name "DQ_14") (class "Default")
      (node (ref "J2") (pin "49") (pinfunction "DQ14_49") (pintype "bidirectional"))
      (node (ref "U9") (pin "133") (pinfunction "P800/D14_133") (pintype "bidirectional"))
    )
    (net (code "62") (name "DQ_15") (class "Default")
      (node (ref "J2") (pin "51") (pinfunction "DQ15_51") (pintype "bidirectional"))
      (node (ref "U9") (pin "134") (pinfunction "P801/D15_134") (pintype "bidirectional"))
    )
    (net (code "63") (name "FG") (class "Default")
      (node (ref "C41") (pin "2") (pinfunction "2_2") (pintype "passive"))
      (node (ref "C42") (pin "2") (pinfunction "2_2") (pintype "passive"))
      (node (ref "C43") (pin "2") (pinfunction "2_2") (pintype "passive"))
      (node (ref "C44") (pin "2") (pinfunction "2_2") (pintype "passive"))
      (node (ref "J3") (pin "S1") (pinfunction "S1_S1") (pintype "passive"))
      (node (ref "J3") (pin "S2") (pinfunction "S2_S2") (pintype "passive"))
      (node (ref "M1") (pin "1") (pinfunction "1_1") (pintype "bidirectional"))
      (node (ref "M2") (pin "1") (pinfunction "1_1") (pintype "bidirectional"))
      (node (ref "M3") (pin "1") (pinfunction "1_1") (pintype "bidirectional"))
      (node (ref "M4") (pin "1") (pinfunction "1_1") (pintype "bidirectional"))
    )
    (net (code "64") (name "GND") (class "Default")
      (node (ref "C1") (pin "-") (pinfunction "-_-") (pintype "passive"))
      (node (ref "C10") (pin "2") (pinfunction "P$2_2") (pintype "bidirectional"))
      (node (ref "C11") (pin "2") (pinfunction "P$2_2") (pintype "bidirectional"))
      (node (ref "C12") (pin "2") (pinfunction "P$2_2") (pintype "bidirectional"))
      (node (ref "C13") (pin "1") (pinfunction "1_1") (pintype "passive"))
      (node (ref "C14") (pin "1") (pinfunction "1_1") (pintype "passive"))
      (node (ref "C15") (pin "2") (pinfunction "P$2_2") (pintype "bidirectional"))
      (node (ref "C16") (pin "2") (pinfunction "P$2_2") (pintype "bidirectional"))
      (node (ref "C17") (pin "1") (pinfunction "1_1") (pintype "passive"))
      (node (ref "C18") (pin "1") (pinfunction "1_1") (pintype "passive"))
      (node (ref "C19") (pin "1") (pinfunction "1_1") (pintype "passive"))
      (node (ref "C2") (pin "-") (pinfunction "-_-") (pintype "passive"))
      (node (ref "C20") (pin "1") (pinfunction "1_1") (pintype "passive"))
      (node (ref "C21") (pin "1") (pinfunction "1_1") (pintype "passive"))
      (node (ref "C22") (pin "1") (pinfunction "1_1") (pintype "passive"))
      (node (ref "C23") (pin "1") (pinfunction "1_1") (pintype "passive"))
      (node (ref "C24") (pin "1") (pinfunction "1_1") (pintype "passive"))
      (node (ref "C25") (pin "1") (pinfunction "1_1") (pintype "passive"))
      (node (ref "C26") (pin "1") (pinfunction "1_1") (pintype "passive"))
      (node (ref "C27") (pin "1") (pinfunction "1_1") (pintype "passive"))
      (node (ref "C28") (pin "-") (pinfunction "-_-") (pintype "passive"))
      (node (ref "C29") (pin "1") (pinfunction "1_1") (pintype "passive"))
      (node (ref "C3") (pin "2") (pinfunction "P$2_2") (pintype "bidirectional"))
      (node (ref "C30") (pin "1") (pinfunction "1_1") (pintype "passive"))
      (node (ref "C31") (pin "1") (pinfunction "1_1") (pintype "passive"))
      (node (ref "C32") (pin "1") (pinfunction "1_1") (pintype "passive"))
      (node (ref "C33") (pin "1") (pinfunction "1_1") (pintype "passive"))
      (node (ref "C34") (pin "1") (pinfunction "1_1") (pintype "passive"))
      (node (ref "C35") (pin "1") (pinfunction "1_1") (pintype "passive"))
      (node (ref "C36") (pin "2") (pinfunction "P$2_2") (pintype "bidirectional"))
      (node (ref "C37") (pin "2") (pinfunction "P$2_2") (pintype "bidirectional"))
      (node (ref "C38") (pin "1") (pinfunction "P$1_1") (pintype "bidirectional"))
      (node (ref "C39") (pin "2") (pinfunction "P$2_2") (pintype "bidirectional"))
      (node (ref "C4") (pin "1") (pinfunction "1_1") (pintype "passive"))
      (node (ref "C40") (pin "2") (pinfunction "P$2_2") (pintype "bidirectional"))
      (node (ref "C41") (pin "1") (pinfunction "1_1") (pintype "passive"))
      (node (ref "C42") (pin "1") (pinfunction "1_1") (pintype "passive"))
      (node (ref "C43") (pin "1") (pinfunction "1_1") (pintype "passive"))
      (node (ref "C44") (pin "1") (pinfunction "1_1") (pintype "passive"))
      (node (ref "C45") (pin "1") (pinfunction "P$1_1") (pintype "bidirectional"))
      (node (ref "C46") (pin "1") (pinfunction "P$1_1") (pintype "bidirectional"))
      (node (ref "C47") (pin "2") (pinfunction "P$2_2") (pintype "bidirectional"))
      (node (ref "C48") (pin "2") (pinfunction "P$2_2") (pintype "bidirectional"))
      (node (ref "C5") (pin "1") (pinfunction "1_1") (pintype "passive"))
      (node (ref "C6") (pin "-") (pinfunction "-_-") (pintype "passive"))
      (node (ref "C7") (pin "2") (pinfunction "P$2_2") (pintype "bidirectional"))
      (node (ref "C8") (pin "2") (pinfunction "P$2_2") (pintype "bidirectional"))
      (node (ref "C9") (pin "2") (pinfunction "P$2_2") (pintype "bidirectional"))
      (node (ref "D2") (pin "A") (pinfunction "A_A") (pintype "passive"))
      (node (ref "D3") (pin "1") (pinfunction "1_1") (pintype "passive"))
      (node (ref "D4") (pin "1") (pinfunction "1_1") (pintype "passive"))
      (node (ref "GND") (pin "1") (pinfunction "TP_1") (pintype "input"))
      (node (ref "J1") (pin "1") (pinfunction "1_1") (pintype "bidirectional"))
      (node (ref "J2") (pin "33") (pinfunction "VSS_33") (pintype "power_in"))
      (node (ref "J2") (pin "52") (pinfunction "VSS_52") (pintype "power_in"))
      (node (ref "J3") (pin "4") (pinfunction "4_4") (pintype "passive"))
      (node (ref "J4") (pin "10") (pinfunction "10_10") (pintype "passive"))
      (node (ref "J4") (pin "12") (pinfunction "12_12") (pintype "passive"))
      (node (ref "J4") (pin "14") (pinfunction "14_14") (pintype "passive"))
      (node (ref "J4") (pin "16") (pinfunction "16_16") (pintype "passive"))
      (node (ref "J4") (pin "18") (pinfunction "18_18") (pintype "passive"))
      (node (ref "J4") (pin "20") (pinfunction "20_20") (pintype "passive"))
      (node (ref "J4") (pin "4") (pinfunction "4_4") (pintype "passive"))
      (node (ref "J4") (pin "6") (pinfunction "6_6") (pintype "passive"))
      (node (ref "J4") (pin "8") (pinfunction "8_8") (pintype "passive"))
      (node (ref "J5") (pin "1") (pinfunction "1_1") (pintype "passive"))
      (node (ref "J6") (pin "9") (pinfunction "9_9") (pintype "passive"))
      (node (ref "R1") (pin "2") (pinfunction "P$2_2") (pintype "bidirectional"))
      (node (ref "R10") (pin "2") (pinfunction "P$2_2") (pintype "bidirectional"))
      (node (ref "R12") (pin "1") (pinfunction "P$1_1") (pintype "bidirectional"))
      (node (ref "R13") (pin "1") (pinfunction "P$1_1") (pintype "bidirectional"))
      (node (ref "R16") (pin "1") (pinfunction "P$1_1") (pintype "bidirectional"))
      (node (ref "R18") (pin "2") (pinfunction "2_2") (pintype "passive"))
      (node (ref "R19") (pin "1") (pinfunction "P$1_1") (pintype "bidirectional"))
      (node (ref "R2") (pin "2") (pinfunction "P$2_2") (pintype "bidirectional"))
      (node (ref "R24") (pin "2") (pinfunction "P$2_2") (pintype "passive"))
      (node (ref "R24") (pin "3") (pinfunction "P$3_3") (pintype "passive"))
      (node (ref "R25") (pin "5") (pinfunction "2_5") (pintype "passive"))
      (node (ref "R25") (pin "8") (pinfunction "2_8") (pintype "passive"))
      (node (ref "R6") (pin "2") (pinfunction "P$2_2") (pintype "bidirectional"))
      (node (ref "R7") (pin "2") (pinfunction "P$2_2") (pintype "bidirectional"))
      (node (ref "U1") (pin "2") (pinfunction "GND_2") (pintype "power_in"))
      (node (ref "U10") (pin "1") (pinfunction "GND_1") (pintype "bidirectional"))
      (node (ref "U11") (pin "3") (pinfunction "GND_3") (pintype "bidirectional"))
      (node (ref "U12") (pin "3") (pinfunction "GND_3") (pintype "passive"))
      (node (ref "U12") (pin "7") (pinfunction "VSS_7") (pintype "passive"))
      (node (ref "U13") (pin "7") (pinfunction "GND_7") (pintype "power_in"))
      (node (ref "U14") (pin "12") (pinfunction "A_12") (pintype "input"))
      (node (ref "U14") (pin "13") (pinfunction "B_13") (pintype "input"))
      (node (ref "U14") (pin "7") (pinfunction "GND_7") (pintype "power_in"))
      (node (ref "U16") (pin "4") (pinfunction "GND_4") (pintype "power_in"))
      (node (ref "U2") (pin "2") (pinfunction "GND_2") (pintype "power_in"))
      (node (ref "U3") (pin "2") (pinfunction "GND_2") (pintype "input"))
      (node (ref "U4") (pin "5") (pinfunction "GND_5") (pintype "bidirectional"))
      (node (ref "U5") (pin "11") (pinfunction "V-_11") (pintype "power_in"))
      (node (ref "U6") (pin "4") (pinfunction "GND_4") (pintype "input"))
      (node (ref "U7") (pin "2") (pinfunction "GND_2") (pintype "power_in"))
      (node (ref "U8") (pin "2") (pinfunction "GND_2") (pintype "power_in"))
      (node (ref "U9") (pin "111") (pinfunction "GND7_111") (pintype "bidirectional"))
      (node (ref "U9") (pin "124") (pinfunction "GND8_124") (pintype "bidirectional"))
      (node (ref "U9") (pin "139") (pinfunction "GND9_139") (pintype "bidirectional"))
      (node (ref "U9") (pin "150") (pinfunction "GND10_150") (pintype "bidirectional"))
      (node (ref "U9") (pin "153") (pinfunction "VREFL_153") (pintype "bidirectional"))
      (node (ref "U9") (pin "156") (pinfunction "AVSS0_156") (pintype "bidirectional"))
      (node (ref "U9") (pin "157") (pinfunction "VREFL0_157") (pintype "bidirectional"))
      (node (ref "U9") (pin "170") (pinfunction "GND11_170") (pintype "bidirectional"))
      (node (ref "U9") (pin "22") (pinfunction "GND1_22") (pintype "bidirectional"))
      (node (ref "U9") (pin "28") (pinfunction "AVSS_USBHS_28") (pintype "bidirectional"))
      (node (ref "U9") (pin "29") (pinfunction "PVSS_USNHS_29") (pintype "bidirectional"))
      (node (ref "U9") (pin "30") (pinfunction "VSS2_USBHS_30") (pintype "bidirectional"))
      (node (ref "U9") (pin "33") (pinfunction "VSS1_USBHS_33") (pintype "bidirectional"))
      (node (ref "U9") (pin "35") (pinfunction "GND2_35") (pintype "bidirectional"))
      (node (ref "U9") (pin "45") (pinfunction "VSS_USB_45") (pintype "bidirectional"))
      (node (ref "U9") (pin "60") (pinfunction "GND3_60") (pintype "bidirectional"))
      (node (ref "U9") (pin "63") (pinfunction "GND4_63") (pintype "bidirectional"))
      (node (ref "U9") (pin "66") (pinfunction "VCC_DCDC_66") (pintype "bidirectional"))
      (node (ref "U9") (pin "83") (pinfunction "GND5_83") (pintype "bidirectional"))
      (node (ref "U9") (pin "98") (pinfunction "GND6_98") (pintype "bidirectional"))
      (node (ref "Y1") (pin "2") (pinfunction "GND_2") (pintype "power_in"))
    )
    (net (code "65") (name "IO_RS485_RXD") (class "Default")
      (node (ref "U4") (pin "1") (pinfunction "R_1") (pintype "bidirectional"))
      (node (ref "U9") (pin "43") (pinfunction "P408/RXD3_A_43") (pintype "bidirectional"))
    )
    (net (code "66") (name "IO_RS485_TE_RE") (class "Default")
      (node (ref "U4") (pin "2") (pinfunction "RE*_2") (pintype "bidirectional"))
      (node (ref "U4") (pin "3") (pinfunction "TE_3") (pintype "bidirectional"))
      (node (ref "U9") (pin "44") (pinfunction "P407_44") (pintype "bidirectional"))
    )
    (net (code "67") (name "IO_RS485_TXD") (class "Default")
      (node (ref "U4") (pin "4") (pinfunction "T_4") (pintype "bidirectional"))
      (node (ref "U9") (pin "42") (pinfunction "P409/TXD3_A_42") (pintype "bidirectional"))
    )
    (net (code "68") (name "LED") (class "Default")
      (node (ref "D7") (pin "C") (pinfunction "1_C") (pintype "passive"))
      (node (ref "U9") (pin "38") (pinfunction "P413_38") (pintype "bidirectional"))
    )
    (net (code "69") (name "Net-(C3-P$1)") (class "Default")
      (node (ref "C2") (pin "+") (pinfunction "+_+") (pintype "passive"))
      (node (ref "C3") (pin "1") (pinfunction "P$1_1") (pintype "bidirectional"))
      (node (ref "D1") (pin "C") (pinfunction "C_C") (pintype "passive"))
      (node (ref "D2") (pin "C") (pinfunction "C_C") (pintype "passive"))
      (node (ref "U3") (pin "1") (pinfunction "IN_1") (pintype "input"))
    )
    (net (code "70") (name "Net-(C28-Pad+)") (class "Default")
      (node (ref "C28") (pin "+") (pinfunction "+_+") (pintype "passive"))
      (node (ref "J3") (pin "1") (pinfunction "1_1") (pintype "passive"))
      (node (ref "PF1") (pin "2") (pinfunction "2_2") (pintype "passive"))
      (node (ref "R18") (pin "1") (pinfunction "1_1") (pintype "passive"))
    )
    (net (code "71") (name "Net-(C45-P$2)") (class "Default")
      (node (ref "C45") (pin "2") (pinfunction "P$2_2") (pintype "bidirectional"))
      (node (ref "D6") (pin "A") (pinfunction "A_A") (pintype "passive"))
      (node (ref "R21") (pin "2") (pinfunction "P$2_2") (pintype "bidirectional"))
      (node (ref "R22") (pin "1") (pinfunction "P$1_1") (pintype "bidirectional"))
      (node (ref "U15") (pin "1") (pinfunction "ADJ_1") (pintype "input"))
    )
    (net (code "72") (name "Net-(D7-2)") (class "Default")
      (node (ref "D7") (pin "A") (pinfunction "2_A") (pintype "passive"))
      (node (ref "R17") (pin "8") (pinfunction "2_8") (pintype "passive"))
    )
    (net (code "73") (name "Net-(EBCLK-TP)") (class "Default")
      (node (ref "EBCLK") (pin "1") (pinfunction "TP_1") (pintype "input"))
      (node (ref "U9") (pin "120") (pinfunction "P602/EBCLK_120") (pintype "bidirectional"))
    )
    (net (code "74") (name "Net-(R1-P$1)") (class "Default")
      (node (ref "R1") (pin "1") (pinfunction "P$1_1") (pintype "bidirectional"))
      (node (ref "R3") (pin "2") (pinfunction "P$2_2") (pintype "bidirectional"))
      (node (ref "U5") (pin "2") (pinfunction "-_2") (pintype "input"))
    )
    (net (code "75") (name "Net-(R2-P$1)") (class "Default")
      (node (ref "R2") (pin "1") (pinfunction "P$1_1") (pintype "bidirectional"))
      (node (ref "R4") (pin "1") (pinfunction "P$1_1") (pintype "bidirectional"))
      (node (ref "U5") (pin "6") (pinfunction "-_6") (pintype "input"))
    )
    (net (code "76") (name "Net-(R5-P$1)") (class "Default")
      (node (ref "J1") (pin "3") (pinfunction "3_3") (pintype "bidirectional"))
      (node (ref "R5") (pin "1") (pinfunction "P$1_1") (pintype "bidirectional"))
      (node (ref "U4") (pin "6") (pinfunction "A_6") (pintype "bidirectional"))
    )
    (net (code "77") (name "Net-(R5-P$2)") (class "Default")
      (node (ref "J1") (pin "4") (pinfunction "4_4") (pintype "bidirectional"))
      (node (ref "R5") (pin "2") (pinfunction "P$2_2") (pintype "bidirectional"))
      (node (ref "U4") (pin "7") (pinfunction "B_7") (pintype "bidirectional"))
    )
    (net (code "78") (name "Net-(R6-P$1)") (class "Default")
      (node (ref "R6") (pin "1") (pinfunction "P$1_1") (pintype "bidirectional"))
      (node (ref "R8") (pin "2") (pinfunction "P$2_2") (pintype "bidirectional"))
      (node (ref "U5") (pin "9") (pinfunction "-_9") (pintype "input"))
    )
    (net (code "79") (name "Net-(R7-P$1)") (class "Default")
      (node (ref "R7") (pin "1") (pinfunction "P$1_1") (pintype "bidirectional"))
      (node (ref "R9") (pin "2") (pinfunction "P$2_2") (pintype "bidirectional"))
      (node (ref "U5") (pin "13") (pinfunction "-_13") (pintype "input"))
    )
    (net (code "80") (name "Net-(R10-P$1)") (class "Default")
      (node (ref "R10") (pin "1") (pinfunction "P$1_1") (pintype "bidirectional"))
      (node (ref "U9") (pin "27") (pinfunction "USBHS_RREF_27") (pintype "bidirectional"))
    )
    (net (code "81") (name "Net-(R12-P$2)") (class "Default")
      (node (ref "R12") (pin "2") (pinfunction "P$2_2") (pintype "bidirectional"))
      (node (ref "U9") (pin "64") (pinfunction "VLO1_64") (pintype "bidirectional"))
      (node (ref "U9") (pin "65") (pinfunction "VLO2_65") (pintype "bidirectional"))
    )
    (net (code "82") (name "Net-(R14-P$2)") (class "Default")
      (node (ref "D3") (pin "2") (pinfunction "2_2") (pintype "passive"))
      (node (ref "J3") (pin "2") (pinfunction "2_2") (pintype "passive"))
      (node (ref "R14") (pin "2") (pinfunction "P$2_2") (pintype "bidirectional"))
      (node (ref "R16") (pin "2") (pinfunction "P$2_2") (pintype "bidirectional"))
    )
    (net (code "83") (name "Net-(R15-P$2)") (class "Default")
      (node (ref "D4") (pin "2") (pinfunction "2_2") (pintype "passive"))
      (node (ref "J3") (pin "3") (pinfunction "3_3") (pintype "passive"))
      (node (ref "R15") (pin "2") (pinfunction "P$2_2") (pintype "bidirectional"))
      (node (ref "R19") (pin "2") (pinfunction "P$2_2") (pintype "bidirectional"))
    )
    (net (code "84") (name "Net-(R17B-2)") (class "Default")
      (node (ref "R17") (pin "7") (pinfunction "2_7") (pintype "passive"))
      (node (ref "U9") (pin "68") (pinfunction "P201/MD_68") (pintype "bidirectional"))
    )
    (net (code "85") (name "Net-(R17C-2)") (class "Default")
      (node (ref "R17") (pin "6") (pinfunction "2_6") (pintype "passive"))
      (node (ref "U9") (pin "69") (pinfunction "P200/NMI_69") (pintype "bidirectional"))
    )
    (net (code "86") (name "Net-(R22-P$2)") (class "Default")
      (node (ref "R22") (pin "2") (pinfunction "P$2_2") (pintype "bidirectional"))
      (node (ref "R23") (pin "2") (pinfunction "P$2_2") (pintype "bidirectional"))
    )
    (net (code "87") (name "Net-(R23-P$1)") (class "Default")
      (node (ref "R23") (pin "1") (pinfunction "P$1_1") (pintype "bidirectional"))
      (node (ref "R24") (pin "1") (pinfunction "P$1_1") (pintype "passive"))
    )
    (net (code "88") (name "Net-(R25B-1)") (class "Default")
      (node (ref "R25") (pin "2") (pinfunction "1_2") (pintype "passive"))
      (node (ref "U9") (pin "168") (pinfunction "P001_168") (pintype "bidirectional"))
    )
    (net (code "89") (name "Net-(R25D-1)") (class "Default")
      (node (ref "R25") (pin "4") (pinfunction "1_4") (pintype "passive"))
      (node (ref "U9") (pin "151") (pinfunction "P015_151") (pintype "bidirectional"))
      (node (ref "U9") (pin "152") (pinfunction "P014_152") (pintype "bidirectional"))
      (node (ref "U9") (pin "159") (pinfunction "P010_159") (pintype "bidirectional"))
      (node (ref "U9") (pin "160") (pinfunction "P009_160") (pintype "bidirectional"))
      (node (ref "U9") (pin "161") (pinfunction "P008_161") (pintype "bidirectional"))
      (node (ref "U9") (pin "162") (pinfunction "P007_162") (pintype "bidirectional"))
      (node (ref "U9") (pin "163") (pinfunction "P006_163") (pintype "bidirectional"))
      (node (ref "U9") (pin "164") (pinfunction "P005_164") (pintype "bidirectional"))
      (node (ref "U9") (pin "165") (pinfunction "P004_165") (pintype "bidirectional"))
      (node (ref "U9") (pin "166") (pinfunction "P003_166") (pintype "bidirectional"))
      (node (ref "U9") (pin "167") (pinfunction "P002_167") (pintype "bidirectional"))
      (node (ref "U9") (pin "169") (pinfunction "P000_169") (pintype "bidirectional"))
    )
    (net (code "90") (name "Net-(TP1-TP)") (class "Default")
      (node (ref "TP1") (pin "1") (pinfunction "TP_1") (pintype "input"))
      (node (ref "U9") (pin "13") (pinfunction "P705_13") (pintype "bidirectional"))
    )
    (net (code "91") (name "Net-(TP2-TP)") (class "Default")
      (node (ref "TP2") (pin "1") (pinfunction "TP_1") (pintype "input"))
      (node (ref "U9") (pin "12") (pinfunction "P704_12") (pintype "bidirectional"))
    )
    (net (code "92") (name "Net-(TP3-TP)") (class "Default")
      (node (ref "TP3") (pin "1") (pinfunction "TP_1") (pintype "input"))
      (node (ref "U9") (pin "11") (pinfunction "P703_11") (pintype "bidirectional"))
    )
    (net (code "93") (name "Net-(TP4-TP)") (class "Default")
      (node (ref "TP4") (pin "1") (pinfunction "TP_1") (pintype "input"))
      (node (ref "U9") (pin "10") (pinfunction "P702_10") (pintype "bidirectional"))
    )
    (net (code "94") (name "Net-(U1-VOUT)") (class "Default")
      (node (ref "U1") (pin "1") (pinfunction "VOUT_1") (pintype "output"))
      (node (ref "U5") (pin "3") (pinfunction "+_3") (pintype "input"))
    )
    (net (code "95") (name "Net-(U2-VOUT)") (class "Default")
      (node (ref "U2") (pin "1") (pinfunction "VOUT_1") (pintype "output"))
      (node (ref "U5") (pin "5") (pinfunction "+_5") (pintype "input"))
    )
    (net (code "96") (name "Net-(U5C-+)") (class "Default")
      (node (ref "U5") (pin "10") (pinfunction "+_10") (pintype "input"))
      (node (ref "U7") (pin "1") (pinfunction "VOUT_1") (pintype "output"))
    )
    (net (code "97") (name "Net-(U5D-+)") (class "Default")
      (node (ref "U5") (pin "12") (pinfunction "+_12") (pintype "input"))
      (node (ref "U8") (pin "1") (pinfunction "VOUT_1") (pintype "output"))
    )
    (net (code "98") (name "Net-(U9-P212{slash}EXTAL)") (class "Default")
      (node (ref "U9") (pin "24") (pinfunction "P212/EXTAL_24") (pintype "bidirectional"))
      (node (ref "Y1") (pin "3") (pinfunction "OUT_3") (pintype "output"))
    )
    (net (code "99") (name "Net-(U9-VCL0)") (class "Default")
      (node (ref "C17") (pin "2") (pinfunction "2_2") (pintype "passive"))
      (node (ref "U9") (pin "19") (pinfunction "VCL0_19") (pintype "bidirectional"))
    )
    (net (code "100") (name "Net-(U9-VCL1)") (class "Default")
      (node (ref "C18") (pin "2") (pinfunction "2_2") (pintype "passive"))
      (node (ref "U9") (pin "62") (pinfunction "VCL1_62") (pintype "bidirectional"))
    )
    (net (code "101") (name "Net-(U9-VCL2)") (class "Default")
      (node (ref "C19") (pin "2") (pinfunction "2_2") (pintype "passive"))
      (node (ref "U9") (pin "148") (pinfunction "VCL2_148") (pintype "bidirectional"))
    )
    (net (code "102") (name "Net-(U9-VCL_F)") (class "Default")
      (node (ref "C21") (pin "2") (pinfunction "2_2") (pintype "passive"))
      (node (ref "U9") (pin "112") (pinfunction "VCL_F_112") (pintype "bidirectional"))
    )
    (net (code "103") (name "Net-(U9-XCIN)") (class "Default")
      (node (ref "R25") (pin "1") (pinfunction "1_1") (pintype "passive"))
      (node (ref "U9") (pin "20") (pinfunction "XCIN_20") (pintype "bidirectional"))
    )
    (net (code "104") (name "Net-(U10-OUT1)") (class "Default")
      (node (ref "C24") (pin "2") (pinfunction "2_2") (pintype "passive"))
      (node (ref "PF1") (pin "1") (pinfunction "1_1") (pintype "passive"))
      (node (ref "U10") (pin "6") (pinfunction "OUT1_6") (pintype "bidirectional"))
      (node (ref "U10") (pin "7") (pinfunction "OUT2_7") (pintype "bidirectional"))
      (node (ref "U10") (pin "8") (pinfunction "OUT3_8") (pintype "bidirectional"))
    )
    (net (code "105") (name "Net-(U13A-Y)") (class "Default")
      (node (ref "U13") (pin "10") (pinfunction "B_10") (pintype "input"))
      (node (ref "U13") (pin "3") (pinfunction "Y_3") (pintype "output"))
    )
    (net (code "106") (name "Net-(U13B-Y)") (class "Default")
      (node (ref "U13") (pin "6") (pinfunction "Y_6") (pintype "output"))
      (node (ref "U13") (pin "9") (pinfunction "A_9") (pintype "input"))
    )
    (net (code "107") (name "Net-(U13C-Y)") (class "Default")
      (node (ref "U13") (pin "12") (pinfunction "A_12") (pintype "input"))
      (node (ref "U13") (pin "8") (pinfunction "Y_8") (pintype "output"))
    )
    (net (code "108") (name "Net-(U13D-B)") (class "Default")
      (node (ref "U13") (pin "13") (pinfunction "B_13") (pintype "input"))
      (node (ref "U14") (pin "8") (pinfunction "Y_8") (pintype "output"))
    )
    (net (code "109") (name "Net-(U14A-Y)") (class "Default")
      (node (ref "U14") (pin "10") (pinfunction "B_10") (pintype "input"))
      (node (ref "U14") (pin "3") (pinfunction "Y_3") (pintype "output"))
    )
    (net (code "110") (name "Net-(U14B-Y)") (class "Default")
      (node (ref "U14") (pin "6") (pinfunction "Y_6") (pintype "output"))
      (node (ref "U14") (pin "9") (pinfunction "A_9") (pintype "input"))
    )
    (net (code "111") (name "OE#") (class "Default")
      (node (ref "J2") (pin "34") (pinfunction "OE#_34") (pintype "input"))
      (node (ref "J6") (pin "2") (pinfunction "2_2") (pintype "passive"))
      (node (ref "U9") (pin "122") (pinfunction "P600/RD_122") (pintype "bidirectional"))
    )
    (net (code "112") (name "QSPI_CS") (class "Default")
      (node (ref "U16") (pin "1") (pinfunction "~{CE}_1") (pintype "input"))
      (node (ref "U9") (pin "141") (pinfunction "P501/QSPI_CS_141") (pintype "bidirectional"))
    )
    (net (code "113") (name "QSPI_D0") (class "Default")
      (node (ref "U16") (pin "5") (pinfunction "SI(IO0)_5") (pintype "bidirectional"))
      (node (ref "U9") (pin "142") (pinfunction "P502/QSPI_IO_0_142") (pintype "bidirectional"))
    )
    (net (code "114") (name "QSPI_D1") (class "Default")
      (node (ref "U16") (pin "2") (pinfunction "SO(IO1)_2") (pintype "bidirectional"))
      (node (ref "U9") (pin "143") (pinfunction "P503/QSPI_IO_1_143") (pintype "bidirectional"))
    )
    (net (code "115") (name "QSPI_D2") (class "Default")
      (node (ref "U16") (pin "3") (pinfunction "~{WP}(IO2)_3") (pintype "bidirectional"))
      (node (ref "U9") (pin "144") (pinfunction "P504/QSPI_IO_2_144") (pintype "bidirectional"))
    )
    (net (code "116") (name "QSPI_D3") (class "Default")
      (node (ref "U16") (pin "7") (pinfunction "~{HOLD}(IO3)_7") (pintype "bidirectional"))
      (node (ref "U9") (pin "145") (pinfunction "P505/QSPI_IO_3_145") (pintype "bidirectional"))
    )
    (net (code "117") (name "QSPI_SCK") (class "Default")
      (node (ref "U16") (pin "6") (pinfunction "SCK_6") (pintype "input"))
      (node (ref "U9") (pin "140") (pinfunction "P500/QSPI_CLK_140") (pintype "bidirectional"))
    )
    (net (code "118") (name "RESET#") (class "Default")
      (node (ref "J4") (pin "15") (pinfunction "15_15") (pintype "passive"))
      (node (ref "R25") (pin "3") (pinfunction "1_3") (pintype "passive"))
      (node (ref "U11") (pin "1") (pinfunction "RESET*_1") (pintype "bidirectional"))
      (node (ref "U9") (pin "67") (pinfunction "~{RESET}_67") (pintype "bidirectional"))
    )
    (net (code "119") (name "RY{slash}BY#") (class "Default")
      (node (ref "J2") (pin "17") (pinfunction "RY/BY#_17") (pintype "output"))
      (node (ref "J6") (pin "5") (pinfunction "5_5") (pintype "passive"))
      (node (ref "U9") (pin "50") (pinfunction "P206/WAIT_50") (pintype "bidirectional"))
    )
    (net (code "120") (name "SCLK") (class "Default")
      (node (ref "U1") (pin "5") (pinfunction "SCLK_5") (pintype "input"))
      (node (ref "U2") (pin "5") (pinfunction "SCLK_5") (pintype "input"))
      (node (ref "U7") (pin "5") (pinfunction "SCLK_5") (pintype "input"))
      (node (ref "U8") (pin "5") (pinfunction "SCLK_5") (pintype "input"))
      (node (ref "U9") (pin "135") (pinfunction "P802_135") (pintype "bidirectional"))
    )
    (net (code "121") (name "SPARE_ANA") (class "Default")
      (node (ref "R9") (pin "1") (pinfunction "P$1_1") (pintype "bidirectional"))
      (node (ref "SPARE_ANA") (pin "1") (pinfunction "TP_1") (pintype "input"))
      (node (ref "U5") (pin "14") (pinfunction "OUT_14") (pintype "output"))
    )
    (net (code "122") (name "SPARE_DAC") (class "Default")
      (node (ref "U8") (pin "4") (pinfunction "DIN_4") (pintype "input"))
      (node (ref "U9") (pin "1") (pinfunction "P400_1") (pintype "bidirectional"))
    )
    (net (code "123") (name "SYNC") (class "Default")
      (node (ref "U1") (pin "6") (pinfunction "SYNC_6") (pintype "input"))
      (node (ref "U2") (pin "6") (pinfunction "SYNC_6") (pintype "input"))
      (node (ref "U7") (pin "6") (pinfunction "SYNC_6") (pintype "input"))
      (node (ref "U8") (pin "6") (pinfunction "SYNC_6") (pintype "input"))
      (node (ref "U9") (pin "136") (pinfunction "P803_136") (pintype "bidirectional"))
    )
    (net (code "124") (name "TCK_SWCLK") (class "Default")
      (node (ref "J4") (pin "9") (pinfunction "9_9") (pintype "passive"))
      (node (ref "R20") (pin "4") (pinfunction "1_4") (pintype "passive"))
      (node (ref "U9") (pin "88") (pinfunction "P300/TCK/SWCLK_88") (pintype "bidirectional"))
    )
    (net (code "125") (name "TDI") (class "Default")
      (node (ref "J4") (pin "5") (pinfunction "5_5") (pintype "passive"))
      (node (ref "R20") (pin "1") (pinfunction "1_1") (pintype "passive"))
      (node (ref "U9") (pin "91") (pinfunction "P110/TDI_91") (pintype "bidirectional"))
    )
    (net (code "126") (name "TDO") (class "Default")
      (node (ref "J4") (pin "13") (pinfunction "13_13") (pintype "passive"))
      (node (ref "R20") (pin "2") (pinfunction "1_2") (pintype "passive"))
      (node (ref "U9") (pin "90") (pinfunction "P109/TDO_90") (pintype "bidirectional"))
    )
    (net (code "127") (name "TMS_SWDIO") (class "Default")
      (node (ref "J4") (pin "7") (pinfunction "7_7") (pintype "passive"))
      (node (ref "R20") (pin "3") (pinfunction "1_3") (pintype "passive"))
      (node (ref "U9") (pin "89") (pinfunction "P108/TMS/SWDIO_89") (pintype "bidirectional"))
    )
    (net (code "128") (name "USB_D_N") (class "Default")
      (node (ref "R14") (pin "1") (pinfunction "P$1_1") (pintype "bidirectional"))
      (node (ref "U9") (pin "31") (pinfunction "USBHS_DM_31") (pintype "bidirectional"))
    )
    (net (code "129") (name "USB_D_P") (class "Default")
      (node (ref "R15") (pin "1") (pinfunction "P$1_1") (pintype "bidirectional"))
      (node (ref "U9") (pin "32") (pinfunction "USBHS_DP_32") (pintype "bidirectional"))
    )
    (net (code "130") (name "USB_OVER_CRNT") (class "Default")
      (node (ref "R11") (pin "2") (pinfunction "P$2_2") (pintype "bidirectional"))
      (node (ref "U10") (pin "5") (pinfunction "OCN_5") (pintype "bidirectional"))
      (node (ref "U9") (pin "15") (pinfunction "P707/USBHS_OVER_CRNT_15") (pintype "bidirectional"))
    )
    (net (code "131") (name "USB_VBUS_EN") (class "Default")
      (node (ref "R13") (pin "2") (pinfunction "P$2_2") (pintype "bidirectional"))
      (node (ref "U10") (pin "4") (pinfunction "EN_4") (pintype "bidirectional"))
      (node (ref "U9") (pin "16") (pinfunction "PB00/USBHS_VBUS_EN_16") (pintype "bidirectional"))
    )
    (net (code "132") (name "VCC") (class "Default")
      (node (ref "C10") (pin "1") (pinfunction "P$1_1") (pintype "bidirectional"))
      (node (ref "C11") (pin "1") (pinfunction "P$1_1") (pintype "bidirectional"))
      (node (ref "C12") (pin "1") (pinfunction "P$1_1") (pintype "bidirectional"))
      (node (ref "C13") (pin "2") (pinfunction "2_2") (pintype "passive"))
      (node (ref "C14") (pin "2") (pinfunction "2_2") (pintype "passive"))
      (node (ref "C15") (pin "1") (pinfunction "P$1_1") (pintype "bidirectional"))
      (node (ref "C23") (pin "2") (pinfunction "2_2") (pintype "passive"))
      (node (ref "C25") (pin "2") (pinfunction "2_2") (pintype "passive"))
      (node (ref "C26") (pin "2") (pinfunction "2_2") (pintype "passive"))
      (node (ref "C27") (pin "2") (pinfunction "2_2") (pintype "passive"))
      (node (ref "C29") (pin "2") (pinfunction "2_2") (pintype "passive"))
      (node (ref "C30") (pin "2") (pinfunction "2_2") (pintype "passive"))
      (node (ref "C31") (pin "2") (pinfunction "2_2") (pintype "passive"))
      (node (ref "C32") (pin "2") (pinfunction "2_2") (pintype "passive"))
      (node (ref "C33") (pin "2") (pinfunction "2_2") (pintype "passive"))
      (node (ref "C34") (pin "2") (pinfunction "2_2") (pintype "passive"))
      (node (ref "C35") (pin "2") (pinfunction "2_2") (pintype "passive"))
      (node (ref "C36") (pin "1") (pinfunction "P$1_1") (pintype "bidirectional"))
      (node (ref "C37") (pin "1") (pinfunction "P$1_1") (pintype "bidirectional"))
      (node (ref "C39") (pin "1") (pinfunction "P$1_1") (pintype "bidirectional"))
      (node (ref "C4") (pin "2") (pinfunction "2_2") (pintype "passive"))
      (node (ref "C40") (pin "1") (pinfunction "P$1_1") (pintype "bidirectional"))
      (node (ref "C5") (pin "2") (pinfunction "2_2") (pintype "passive"))
      (node (ref "C8") (pin "1") (pinfunction "P$1_1") (pintype "bidirectional"))
      (node (ref "C9") (pin "1") (pinfunction "P$1_1") (pintype "bidirectional"))
      (node (ref "J2") (pin "29") (pinfunction "VIO_29") (pintype "power_in"))
      (node (ref "J2") (pin "43") (pinfunction "VCC_43") (pintype "power_in"))
      (node (ref "J4") (pin "1") (pinfunction "1_1") (pintype "passive"))
      (node (ref "J5") (pin "3") (pinfunction "3_3") (pintype "passive"))
      (node (ref "R11") (pin "1") (pinfunction "P$1_1") (pintype "bidirectional"))
      (node (ref "R17") (pin "1") (pinfunction "1_1") (pintype "passive"))
      (node (ref "R17") (pin "2") (pinfunction "1_2") (pintype "passive"))
      (node (ref "R17") (pin "3") (pinfunction "1_3") (pintype "passive"))
      (node (ref "R20") (pin "5") (pinfunction "2_5") (pintype "passive"))
      (node (ref "R20") (pin "6") (pinfunction "2_6") (pintype "passive"))
      (node (ref "R20") (pin "7") (pinfunction "2_7") (pintype "passive"))
      (node (ref "R20") (pin "8") (pinfunction "2_8") (pintype "passive"))
      (node (ref "R25") (pin "6") (pinfunction "2_6") (pintype "passive"))
      (node (ref "R25") (pin "7") (pinfunction "2_7") (pintype "passive"))
      (node (ref "U1") (pin "3") (pinfunction "VA_3") (pintype "power_in"))
      (node (ref "U11") (pin "2") (pinfunction "VCC_2") (pintype "bidirectional"))
      (node (ref "U13") (pin "14") (pinfunction "VCC_14") (pintype "power_in"))
      (node (ref "U14") (pin "14") (pinfunction "VCC_14") (pintype "power_in"))
      (node (ref "U16") (pin "8") (pinfunction "VCC_8") (pintype "power_in"))
      (node (ref "U2") (pin "3") (pinfunction "VA_3") (pintype "power_in"))
      (node (ref "U4") (pin "8") (pinfunction "V_8") (pintype "bidirectional"))
      (node (ref "U6") (pin "3") (pinfunction "OUT_3") (pintype "passive"))
      (node (ref "U7") (pin "3") (pinfunction "VA_3") (pintype "power_in"))
      (node (ref "U8") (pin "3") (pinfunction "VA_3") (pintype "power_in"))
      (node (ref "U9") (pin "110") (pinfunction "VCC5_110") (pintype "bidirectional"))
      (node (ref "U9") (pin "123") (pinfunction "VCC6_123") (pintype "bidirectional"))
      (node (ref "U9") (pin "138") (pinfunction "VCC7_138") (pintype "bidirectional"))
      (node (ref "U9") (pin "149") (pinfunction "VCC8_149") (pintype "bidirectional"))
      (node (ref "U9") (pin "154") (pinfunction "VREFH_154") (pintype "bidirectional"))
      (node (ref "U9") (pin "155") (pinfunction "AVCC0_155") (pintype "bidirectional"))
      (node (ref "U9") (pin "158") (pinfunction "VREFH0_158") (pintype "bidirectional"))
      (node (ref "U9") (pin "171") (pinfunction "VCC9_171") (pintype "bidirectional"))
      (node (ref "U9") (pin "18") (pinfunction "VBATT_18") (pintype "bidirectional"))
      (node (ref "U9") (pin "25") (pinfunction "VCC1_25") (pintype "bidirectional"))
      (node (ref "U9") (pin "26") (pinfunction "AVCC_USBHS_26") (pintype "bidirectional"))
      (node (ref "U9") (pin "34") (pinfunction "VCC_USBHS_34") (pintype "bidirectional"))
      (node (ref "U9") (pin "48") (pinfunction "VCC_USB_48") (pintype "bidirectional"))
      (node (ref "U9") (pin "61") (pinfunction "VCC2_61") (pintype "bidirectional"))
      (node (ref "U9") (pin "84") (pinfunction "VCC3_84") (pintype "bidirectional"))
      (node (ref "U9") (pin "97") (pinfunction "VCC4_97") (pintype "bidirectional"))
      (node (ref "VCC") (pin "1") (pinfunction "TP_1") (pintype "input"))
      (node (ref "Y1") (pin "4") (pinfunction "VDD_4") (pintype "power_in"))
    )
    (net (code "133") (name "VIN") (class "Default")
      (node (ref "C1") (pin "+") (pinfunction "+_+") (pintype "passive"))
      (node (ref "C48") (pin "1") (pinfunction "P$1_1") (pintype "bidirectional"))
      (node (ref "D1") (pin "A") (pinfunction "A_A") (pintype "passive"))
      (node (ref "D5") (pin "C") (pinfunction "C_C") (pintype "passive"))
      (node (ref "J1") (pin "2") (pinfunction "2_2") (pintype "bidirectional"))
      (node (ref "U15") (pin "3") (pinfunction "IN_3") (pintype "input"))
      (node (ref "VIN") (pin "1") (pinfunction "TP_1") (pintype "input"))
    )
    (net (code "134") (name "WE#") (class "Default")
      (node (ref "J2") (pin "13") (pinfunction "WE#_13") (pintype "input"))
      (node (ref "J6") (pin "3") (pinfunction "3_3") (pintype "passive"))
      (node (ref "U9") (pin "121") (pinfunction "P601/WR/WR0_121") (pintype "bidirectional"))
    )
    (net (code "135") (name "WP_ACC_ANA") (class "Default")
      (node (ref "J2") (pin "16") (pinfunction "WP#_16") (pintype "input"))
      (node (ref "J6") (pin "4") (pinfunction "4_4") (pintype "passive"))
      (node (ref "R4") (pin "2") (pinfunction "P$2_2") (pintype "bidirectional"))
      (node (ref "U5") (pin "7") (pinfunction "OUT_7") (pintype "output"))
    )
    (net (code "136") (name "WP_ACC_DAC") (class "Default")
      (node (ref "U2") (pin "4") (pinfunction "DIN_4") (pintype "input"))
      (node (ref "U9") (pin "175") (pinfunction "P512/TXD4_B/SDA4_B_175") (pintype "bidirectional"))
    )
    (net (code "137") (name "unconnected-(J4-Pad2)") (class "Default")
      (node (ref "J4") (pin "2") (pinfunction "2_2") (pintype "passive"))
    )
    (net (code "138") (name "unconnected-(J4-Pad3)") (class "Default")
      (node (ref "J4") (pin "3") (pinfunction "3_3") (pintype "passive"))
    )
    (net (code "139") (name "unconnected-(J4-Pad11)") (class "Default")
      (node (ref "J4") (pin "11") (pinfunction "11_11") (pintype "passive"))
    )
    (net (code "140") (name "unconnected-(J4-Pad17)") (class "Default")
      (node (ref "J4") (pin "17") (pinfunction "17_17") (pintype "passive"))
    )
    (net (code "141") (name "unconnected-(J4-Pad19)") (class "Default")
      (node (ref "J4") (pin "19") (pinfunction "19_19") (pintype "passive"))
    )
    (net (code "142") (name "unconnected-(J6-Pad6)") (class "Default")
      (node (ref "J6") (pin "6") (pinfunction "6_6") (pintype "passive"))
    )
    (net (code "143") (name "unconnected-(J6-Pad7)") (class "Default")
      (node (ref "J6") (pin "7") (pinfunction "7_7") (pintype "passive"))
    )
    (net (code "144") (name "unconnected-(J6-Pad8)") (class "Default")
      (node (ref "J6") (pin "8") (pinfunction "8_8") (pintype "passive"))
    )
    (net (code "145") (name "unconnected-(U9-P202-Pad54)") (class "Default")
      (node (ref "U9") (pin "54") (pinfunction "P202_54") (pintype "bidirectional"))
    )
    (net (code "146") (name "unconnected-(U9-P213{slash}XTAL{slash}TXD-Pad23)") (class "Default")
      (node (ref "U9") (pin "23") (pinfunction "P213/XTAL/TXD_23") (pintype "bidirectional"))
    )
    (net (code "147") (name "unconnected-(U9-P401-Pad2)") (class "Default")
      (node (ref "U9") (pin "2") (pinfunction "P401_2") (pintype "bidirectional"))
    )
    (net (code "148") (name "unconnected-(U9-P402-Pad3)") (class "Default")
      (node (ref "U9") (pin "3") (pinfunction "P402_3") (pintype "bidirectional"))
    )
    (net (code "149") (name "unconnected-(U9-P403-Pad4)") (class "Default")
      (node (ref "U9") (pin "4") (pinfunction "P403_4") (pintype "bidirectional"))
    )
    (net (code "150") (name "unconnected-(U9-P404-Pad5)") (class "Default")
      (node (ref "U9") (pin "5") (pinfunction "P404_5") (pintype "bidirectional"))
    )
    (net (code "151") (name "unconnected-(U9-P405-Pad6)") (class "Default")
      (node (ref "U9") (pin "6") (pinfunction "P405_6") (pintype "bidirectional"))
    )
    (net (code "152") (name "unconnected-(U9-P406-Pad7)") (class "Default")
      (node (ref "U9") (pin "7") (pinfunction "P406_7") (pintype "bidirectional"))
    )
    (net (code "153") (name "unconnected-(U9-P412-Pad39)") (class "Default")
      (node (ref "U9") (pin "39") (pinfunction "P412_39") (pintype "bidirectional"))
    )
    (net (code "154") (name "unconnected-(U9-P414-Pad37)") (class "Default")
      (node (ref "U9") (pin "37") (pinfunction "P414_37") (pintype "bidirectional"))
    )
    (net (code "155") (name "unconnected-(U9-P415-Pad36)") (class "Default")
      (node (ref "U9") (pin "36") (pinfunction "P415_36") (pintype "bidirectional"))
    )
    (net (code "156") (name "unconnected-(U9-P506-Pad146)") (class "Default")
      (node (ref "U9") (pin "146") (pinfunction "P506_146") (pintype "bidirectional"))
    )
    (net (code "157") (name "unconnected-(U9-P507-Pad147)") (class "Default")
      (node (ref "U9") (pin "147") (pinfunction "P507_147") (pintype "bidirectional"))
    )
    (net (code "158") (name "unconnected-(U9-P608{slash}A00{slash}BC0-Pad99)") (class "Default")
      (node (ref "U9") (pin "99") (pinfunction "P608/A00/BC0_99") (pintype "bidirectional"))
    )
    (net (code "159") (name "unconnected-(U9-P700-Pad8)") (class "Default")
      (node (ref "U9") (pin "8") (pinfunction "P700_8") (pintype "bidirectional"))
    )
    (net (code "160") (name "unconnected-(U9-P701-Pad9)") (class "Default")
      (node (ref "U9") (pin "9") (pinfunction "P701_9") (pintype "bidirectional"))
    )
    (net (code "161") (name "unconnected-(U9-P706{slash}IRQ_7-Pad14)") (class "Default")
      (node (ref "U9") (pin "14") (pinfunction "P706/IRQ_7_14") (pintype "bidirectional"))
    )
    (net (code "162") (name "unconnected-(U9-P805-Pad173)") (class "Default")
      (node (ref "U9") (pin "173") (pinfunction "P805_173") (pintype "bidirectional"))
    )
    (net (code "163") (name "unconnected-(U9-P806-Pad172)") (class "Default")
      (node (ref "U9") (pin "172") (pinfunction "P806_172") (pintype "bidirectional"))
    )
    (net (code "164") (name "unconnected-(U9-P901-Pad59)") (class "Default")
      (node (ref "U9") (pin "59") (pinfunction "P901_59") (pintype "bidirectional"))
    )
    (net (code "165") (name "unconnected-(U9-PA00-Pad114)") (class "Default")
      (node (ref "U9") (pin "114") (pinfunction "PA00_114") (pintype "bidirectional"))
    )
    (net (code "166") (name "unconnected-(U9-PA01-Pad113)") (class "Default")
      (node (ref "U9") (pin "113") (pinfunction "PA01_113") (pintype "bidirectional"))
    )
    (net (code "167") (name "unconnected-(U9-PA08-Pad107)") (class "Default")
      (node (ref "U9") (pin "107") (pinfunction "PA08_107") (pintype "bidirectional"))
    )
    (net (code "168") (name "unconnected-(U9-PA09-Pad108)") (class "Default")
      (node (ref "U9") (pin "108") (pinfunction "PA09_108") (pintype "bidirectional"))
    )
    (net (code "169") (name "unconnected-(U9-PA10-Pad109)") (class "Default")
      (node (ref "U9") (pin "109") (pinfunction "PA10_109") (pintype "bidirectional"))
    )
    (net (code "170") (name "unconnected-(U9-PB01{slash}USBHS_VBUS-Pad17)") (class "Default")
      (node (ref "U9") (pin "17") (pinfunction "PB01/USBHS_VBUS_17") (pintype "bidirectional"))
    )
    (net (code "171") (name "unconnected-(U9-USB_DM-Pad46)") (class "Default")
      (node (ref "U9") (pin "46") (pinfunction "USB_DM_46") (pintype "bidirectional"))
    )
    (net (code "172") (name "unconnected-(U9-USB_DP-Pad47)") (class "Default")
      (node (ref "U9") (pin "47") (pinfunction "USB_DP_47") (pintype "bidirectional"))
    )
    (net (code "173") (name "unconnected-(U9-XCOUT-Pad21)") (class "Default")
      (node (ref "U9") (pin "21") (pinfunction "XCOUT_21") (pintype "bidirectional"))
    )
    (net (code "174") (name "unconnected-(U12-NC-Pad5)") (class "Default")
      (node (ref "U12") (pin "5") (pinfunction "NC_5") (pintype "no_connect"))
    )
    (net (code "175") (name "unconnected-(U14D-Y-Pad11)") (class "Default")
      (node (ref "U14") (pin "11") (pinfunction "Y_11") (pintype "output"))
    )
    (net (code "176") (name "unconnected-(Y1-CTL-Pad1)") (class "Default")
      (node (ref "Y1") (pin "1") (pinfunction "CTL_1") (pintype "passive"))
    )
  )
)
